# Main.net
KiCad netlist of a schematic drawn in Altium Designer
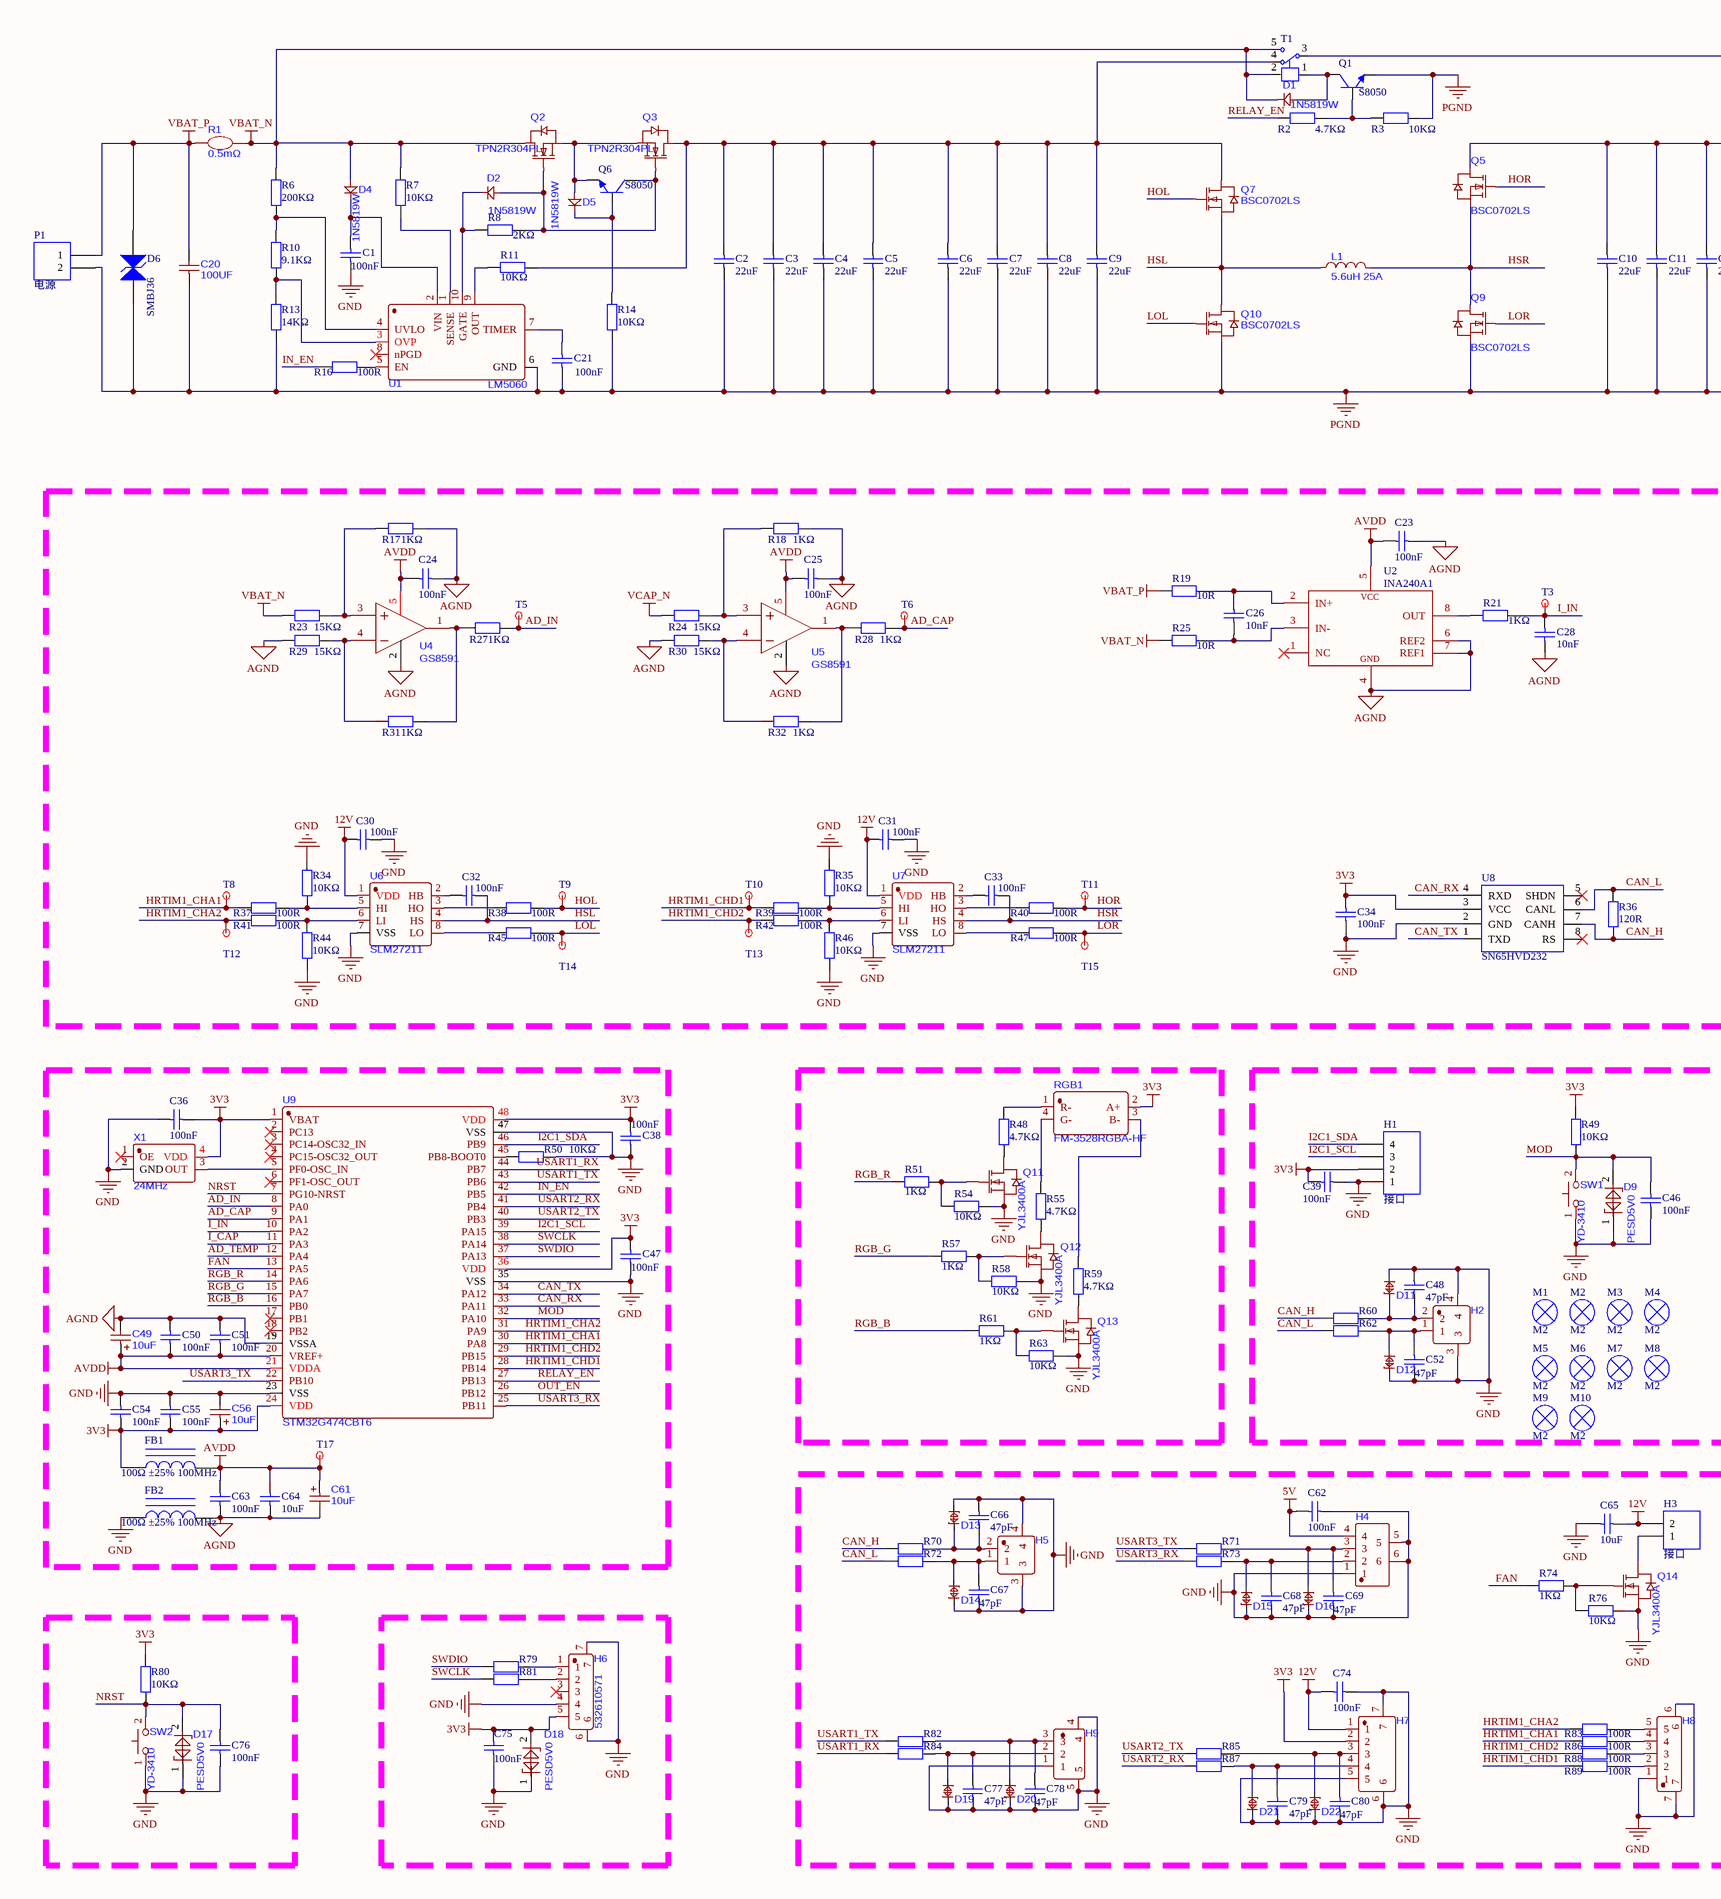
[diagram p0: Main.SchDoc, left]
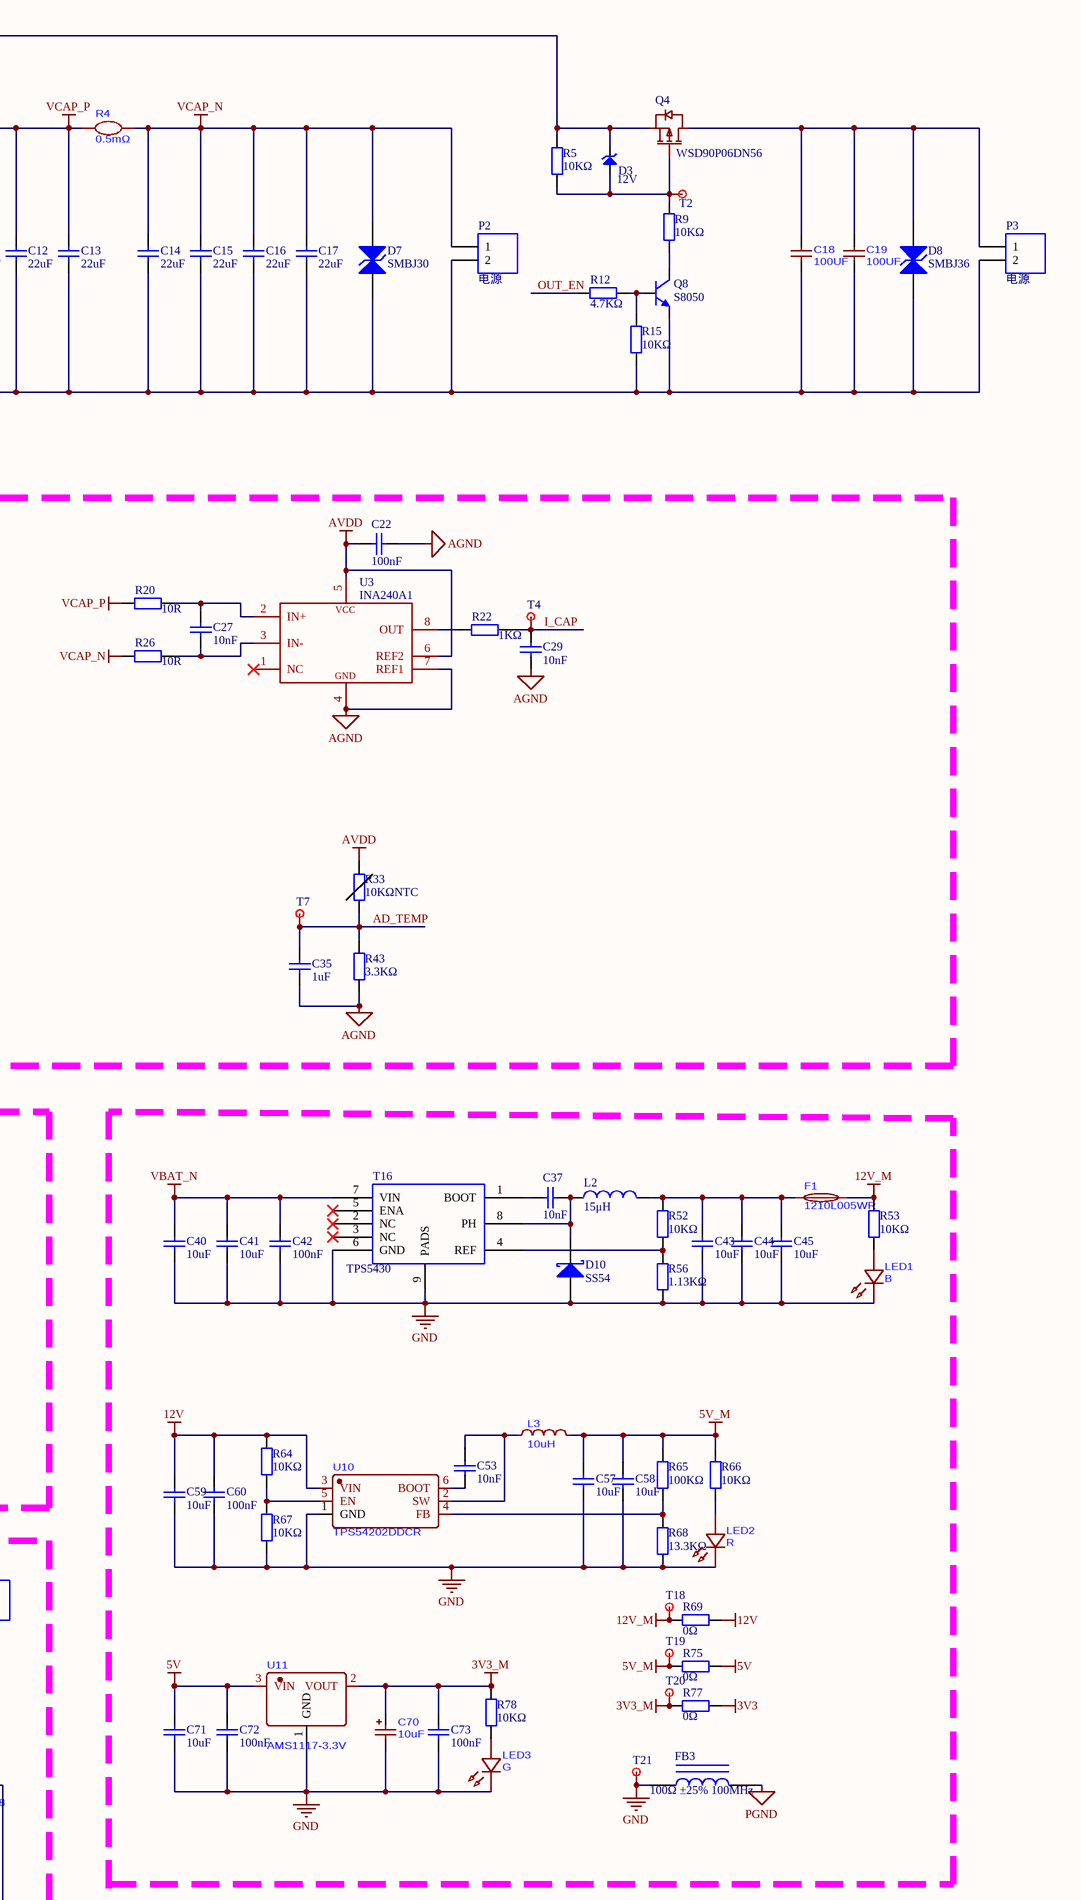
[diagram p1: Main.SchDoc, right]

(export (version "E")
  (design (tool "Eeschema 10.0.6"))
  (components
    (comp (ref "C1")
      (value "100nF")
      (footprint "0402_C")
      (description "贴片电容")
      (libsource (lib "Miscellaneous Devices LC") (part "0402 10nF (103) 10% 50V"))
    )
    (comp (ref "C2")
      (value "22uF")
      (footprint "1206_C")
      (description "贴片电容")
      (libsource (lib "Miscellaneous Devices LC") (part "1206 100nF (104) 10% 50V"))
    )
    (comp (ref "C3")
      (value "22uF")
      (footprint "1206_C")
      (description "贴片电容")
      (libsource (lib "Miscellaneous Devices LC") (part "1206 100nF (104) 10% 50V"))
    )
    (comp (ref "C4")
      (value "22uF")
      (footprint "1206_C")
      (description "贴片电容")
      (libsource (lib "Miscellaneous Devices LC") (part "1206 100nF (104) 10% 50V"))
    )
    (comp (ref "C5")
      (value "22uF")
      (footprint "1206_C")
      (description "贴片电容")
      (libsource (lib "Miscellaneous Devices LC") (part "1206 100nF (104) 10% 50V"))
    )
    (comp (ref "C6")
      (value "22uF")
      (footprint "1206_C")
      (description "贴片电容")
      (libsource (lib "Miscellaneous Devices LC") (part "1206 100nF (104) 10% 50V"))
    )
    (comp (ref "C7")
      (value "22uF")
      (footprint "1206_C")
      (description "贴片电容")
      (libsource (lib "Miscellaneous Devices LC") (part "1206 100nF (104) 10% 50V"))
    )
    (comp (ref "C8")
      (value "22uF")
      (footprint "1206_C")
      (description "贴片电容")
      (libsource (lib "Miscellaneous Devices LC") (part "1206 100nF (104) 10% 50V"))
    )
    (comp (ref "C9")
      (value "22uF")
      (footprint "1206_C")
      (description "贴片电容")
      (libsource (lib "Miscellaneous Devices LC") (part "1206 100nF (104) 10% 50V"))
    )
    (comp (ref "C10")
      (value "22uF")
      (footprint "1206_C")
      (description "贴片电容")
      (libsource (lib "Miscellaneous Devices LC") (part "1206 100nF (104) 10% 50V"))
    )
    (comp (ref "C11")
      (value "22uF")
      (footprint "1206_C")
      (description "贴片电容")
      (libsource (lib "Miscellaneous Devices LC") (part "1206 100nF (104) 10% 50V"))
    )
    (comp (ref "C12")
      (value "22uF")
      (footprint "1206_C")
      (description "贴片电容")
      (libsource (lib "Miscellaneous Devices LC") (part "1206 100nF (104) 10% 50V"))
    )
    (comp (ref "C13")
      (value "22uF")
      (footprint "1206_C")
      (description "贴片电容")
      (libsource (lib "Miscellaneous Devices LC") (part "1206 100nF (104) 10% 50V"))
    )
    (comp (ref "C14")
      (value "22uF")
      (footprint "1206_C")
      (description "贴片电容")
      (libsource (lib "Miscellaneous Devices LC") (part "1206 100nF (104) 10% 50V"))
    )
    (comp (ref "C15")
      (value "22uF")
      (footprint "1206_C")
      (description "贴片电容")
      (libsource (lib "Miscellaneous Devices LC") (part "1206 100nF (104) 10% 50V"))
    )
    (comp (ref "C16")
      (value "22uF")
      (footprint "1206_C")
      (description "贴片电容")
      (libsource (lib "Miscellaneous Devices LC") (part "1206 100nF (104) 10% 50V"))
    )
    (comp (ref "C17")
      (value "22uF")
      (footprint "1206_C")
      (description "贴片电容")
      (libsource (lib "Miscellaneous Devices LC") (part "1206 100nF (104) 10% 50V"))
    )
    (comp (ref "C18")
      (value "100UF")
      (footprint "C1812")
      (description "电容")
      (libsource (lib "JiangCi") (part "100UF/50V-1812"))
    )
    (comp (ref "C19")
      (value "100UF")
      (footprint "C1812")
      (description "电容")
      (libsource (lib "JiangCi") (part "100UF/50V-1812"))
    )
    (comp (ref "C20")
      (value "100UF")
      (footprint "C1812")
      (description "电容")
      (libsource (lib "JiangCi") (part "100UF/50V-1812"))
    )
    (comp (ref "C21")
      (value "100nF")
      (footprint "0402_C")
      (description "贴片电容")
      (libsource (lib "Miscellaneous Devices LC") (part "0402 10nF (103) 10% 50V"))
    )
    (comp (ref "C22")
      (value "100nF")
      (footprint "0402_C")
      (description "贴片电容")
      (libsource (lib "Miscellaneous Devices LC") (part "0402 10nF (103) 10% 50V"))
    )
    (comp (ref "C23")
      (value "100nF")
      (footprint "0402_C")
      (description "贴片电容")
      (libsource (lib "Miscellaneous Devices LC") (part "0402 10nF (103) 10% 50V"))
    )
    (comp (ref "C24")
      (value "100nF")
      (footprint "0402_C")
      (description "贴片电容")
      (libsource (lib "Miscellaneous Devices LC") (part "0402 10nF (103) 10% 50V"))
    )
    (comp (ref "C25")
      (value "100nF")
      (footprint "0402_C")
      (description "贴片电容")
      (libsource (lib "Miscellaneous Devices LC") (part "0402 10nF (103) 10% 50V"))
    )
    (comp (ref "C26")
      (value "10nF")
      (footprint "0402_C")
      (description "贴片电容")
      (libsource (lib "Miscellaneous Devices LC") (part "0402 10nF (103) 10% 50V"))
    )
    (comp (ref "C27")
      (value "10nF")
      (footprint "0402_C")
      (description "贴片电容")
      (libsource (lib "Miscellaneous Devices LC") (part "0402 10nF (103) 10% 50V"))
    )
    (comp (ref "C28")
      (value "10nF")
      (footprint "0402_C")
      (description "贴片电容")
      (libsource (lib "Miscellaneous Devices LC") (part "0402 10nF (103) 10% 50V"))
    )
    (comp (ref "C29")
      (value "10nF")
      (footprint "0402_C")
      (description "贴片电容")
      (libsource (lib "Miscellaneous Devices LC") (part "0402 10nF (103) 10% 50V"))
    )
    (comp (ref "C30")
      (value "100nF")
      (footprint "0402_C")
      (description "贴片电容")
      (libsource (lib "Miscellaneous Devices LC") (part "0402 10nF (103) 10% 50V"))
    )
    (comp (ref "C31")
      (value "100nF")
      (footprint "0402_C")
      (description "贴片电容")
      (libsource (lib "Miscellaneous Devices LC") (part "0402 10nF (103) 10% 50V"))
    )
    (comp (ref "C32")
      (value "100nF")
      (footprint "0402_C")
      (description "贴片电容")
      (libsource (lib "Miscellaneous Devices LC") (part "0402 10nF (103) 10% 50V"))
    )
    (comp (ref "C33")
      (value "100nF")
      (footprint "0402_C")
      (description "贴片电容")
      (libsource (lib "Miscellaneous Devices LC") (part "0402 10nF (103) 10% 50V"))
    )
    (comp (ref "C34")
      (value "100nF")
      (footprint "0402_C")
      (description "贴片电容")
      (libsource (lib "Miscellaneous Devices LC") (part "0402 10nF (103) 10% 50V"))
    )
    (comp (ref "C35")
      (value "1uF")
      (footprint "0402_C")
      (description "贴片电容")
      (libsource (lib "Miscellaneous Devices LC") (part "0402 100nF (104) 10% 16V"))
    )
    (comp (ref "C36")
      (value "100nF")
      (footprint "0402_C")
      (description "贴片电容")
      (libsource (lib "Miscellaneous Devices LC") (part "0402 100nF (104) 10% 16V"))
    )
    (comp (ref "C37")
      (value "10nF")
      (footprint "0402_C")
      (description "贴片电容")
      (libsource (lib "Miscellaneous Devices LC") (part "0402 10nF (103) 10% 50V"))
    )
    (comp (ref "C38")
      (value "100nF")
      (footprint "0402_C")
      (description "贴片电容")
      (libsource (lib "Miscellaneous Devices LC") (part "0402 100nF (104) 10% 16V"))
    )
    (comp (ref "C39")
      (value "100nF")
      (footprint "0402_C")
      (description "贴片电容")
      (libsource (lib "Miscellaneous Devices LC") (part "0402 100nF (104) 10% 16V"))
    )
    (comp (ref "C40")
      (value "10uF")
      (footprint "1206_C")
      (description "贴片电容")
      (libsource (lib "Miscellaneous Devices LC") (part "1206 10uF (106) 10% 50V"))
    )
    (comp (ref "C41")
      (value "10uF")
      (footprint "1206_C")
      (description "贴片电容")
      (libsource (lib "Miscellaneous Devices LC") (part "1206 10uF (106) 10% 50V"))
    )
    (comp (ref "C42")
      (value "100nF")
      (footprint "0603_C")
      (description "贴片电容")
      (libsource (lib "Miscellaneous Devices LC") (part "0603 100nF (104) 10% 50V"))
    )
    (comp (ref "C43")
      (value "10uF")
      (footprint "1206_C")
      (description "贴片电容")
      (libsource (lib "Miscellaneous Devices LC") (part "1206 10uF (106) 10% 50V"))
    )
    (comp (ref "C44")
      (value "10uF")
      (footprint "1206_C")
      (description "贴片电容")
      (libsource (lib "Miscellaneous Devices LC") (part "1206 10uF (106) 10% 50V"))
    )
    (comp (ref "C45")
      (value "10uF")
      (footprint "1206_C")
      (description "贴片电容")
      (libsource (lib "Miscellaneous Devices LC") (part "1206 10uF (106) 10% 50V"))
    )
    (comp (ref "C46")
      (value "100nF")
      (footprint "0402_C")
      (description "贴片电容")
      (libsource (lib "Miscellaneous Devices LC") (part "0402 100nF (104) 10% 16V"))
    )
    (comp (ref "C47")
      (value "100nF")
      (footprint "0402_C")
      (description "贴片电容")
      (libsource (lib "Miscellaneous Devices LC") (part "0402 100nF (104) 10% 16V"))
    )
    (comp (ref "C48")
      (value "47pF")
      (footprint "0402_C")
      (description "贴片电容")
      (libsource (lib "Miscellaneous Devices LC") (part "0402 47pF (470) 5% 50V"))
    )
    (comp (ref "C49")
      (value "10uF")
      (footprint "CAP-SMD_L3.2-W1.6-RD-C7171")
      (libsource (lib "JiangCi") (part "3216钽电容"))
    )
    (comp (ref "C50")
      (value "100nF")
      (footprint "0402_C")
      (description "贴片电容")
      (libsource (lib "Miscellaneous Devices LC") (part "0402 100nF (104) 10% 16V"))
    )
    (comp (ref "C51")
      (value "100nF")
      (footprint "0402_C")
      (description "贴片电容")
      (libsource (lib "Miscellaneous Devices LC") (part "0402 100nF (104) 10% 16V"))
    )
    (comp (ref "C52")
      (value "47pF")
      (footprint "0402_C")
      (description "贴片电容")
      (libsource (lib "Miscellaneous Devices LC") (part "0402 47pF (470) 5% 50V"))
    )
    (comp (ref "C53")
      (value "10nF")
      (footprint "0402_C")
      (description "贴片电容")
      (libsource (lib "Miscellaneous Devices LC") (part "0402 10nF (103) 10% 50V"))
    )
    (comp (ref "C54")
      (value "100nF")
      (footprint "0402_C")
      (description "贴片电容")
      (libsource (lib "Miscellaneous Devices LC") (part "0402 100nF (104) 10% 16V"))
    )
    (comp (ref "C55")
      (value "100nF")
      (footprint "0402_C")
      (description "贴片电容")
      (libsource (lib "Miscellaneous Devices LC") (part "0402 100nF (104) 10% 16V"))
    )
    (comp (ref "C56")
      (value "10uF")
      (footprint "CAP-SMD_L3.2-W1.6-RD-C7171")
      (libsource (lib "JiangCi") (part "3216钽电容"))
    )
    (comp (ref "C57")
      (value "10uF")
      (footprint "1206_C")
      (description "贴片电容")
      (libsource (lib "Miscellaneous Devices LC") (part "1206 10uF (106) 10% 50V"))
    )
    (comp (ref "C58")
      (value "10uF")
      (footprint "1206_C")
      (description "贴片电容")
      (libsource (lib "Miscellaneous Devices LC") (part "1206 10uF (106) 10% 50V"))
    )
    (comp (ref "C59")
      (value "10uF")
      (footprint "1206_C")
      (description "贴片电容")
      (libsource (lib "Miscellaneous Devices LC") (part "1206 10uF (106) 10% 50V"))
    )
    (comp (ref "C60")
      (value "100nF")
      (footprint "0603_C")
      (description "贴片电容")
      (libsource (lib "Miscellaneous Devices LC") (part "0603 100nF (104) 10% 50V"))
    )
    (comp (ref "C61")
      (value "10uF")
      (footprint "CAP-SMD_L3.2-W1.6-RD-C7171")
      (libsource (lib "JiangCi") (part "3216钽电容"))
    )
    (comp (ref "C62")
      (value "100nF")
      (footprint "0402_C")
      (description "贴片电容")
      (libsource (lib "Miscellaneous Devices LC") (part "0402 100nF (104) 10% 16V"))
    )
    (comp (ref "C63")
      (value "100nF")
      (footprint "0402_C")
      (description "贴片电容")
      (libsource (lib "Miscellaneous Devices LC") (part "0402 100nF (104) 10% 16V"))
    )
    (comp (ref "C64")
      (value "10uF")
      (footprint "0402_C")
      (description "贴片电容")
      (libsource (lib "Miscellaneous Devices LC") (part "0402 100nF (104) 10% 16V"))
    )
    (comp (ref "C65")
      (value "10uF")
      (footprint "1206_C")
      (description "贴片电容")
      (libsource (lib "Miscellaneous Devices LC") (part "1206 10uF (106) 10% 50V"))
    )
    (comp (ref "C66")
      (value "47pF")
      (footprint "0402_C")
      (description "贴片电容")
      (libsource (lib "Miscellaneous Devices LC") (part "0402 47pF (470) 5% 50V"))
    )
    (comp (ref "C67")
      (value "47pF")
      (footprint "0402_C")
      (description "贴片电容")
      (libsource (lib "Miscellaneous Devices LC") (part "0402 47pF (470) 5% 50V"))
    )
    (comp (ref "C68")
      (value "47pF")
      (footprint "0402_C")
      (description "贴片电容")
      (libsource (lib "Miscellaneous Devices LC") (part "0402 47pF (470) 5% 50V"))
    )
    (comp (ref "C69")
      (value "47pF")
      (footprint "0402_C")
      (description "贴片电容")
      (libsource (lib "Miscellaneous Devices LC") (part "0402 47pF (470) 5% 50V"))
    )
    (comp (ref "C70")
      (value "10uF")
      (footprint "CAP-SMD_L3.2-W1.6-RD-C7171")
      (libsource (lib "JiangCi") (part "3216钽电容"))
    )
    (comp (ref "C71")
      (value "10uF")
      (footprint "0603_C")
      (description "贴片电容")
      (libsource (lib "Miscellaneous Devices LC") (part "0603 100nF (104) 10% 50V"))
    )
    (comp (ref "C72")
      (value "100nF")
      (footprint "0603_C")
      (description "贴片电容")
      (libsource (lib "Miscellaneous Devices LC") (part "0603 100nF (104) 10% 50V"))
    )
    (comp (ref "C73")
      (value "100nF")
      (footprint "0603_C")
      (description "贴片电容")
      (libsource (lib "Miscellaneous Devices LC") (part "0603 100nF (104) 10% 50V"))
    )
    (comp (ref "C74")
      (value "100nF")
      (footprint "0402_C")
      (description "贴片电容")
      (libsource (lib "Miscellaneous Devices LC") (part "0402 100nF (104) 10% 16V"))
    )
    (comp (ref "C75")
      (value "100nF")
      (footprint "0402_C")
      (description "贴片电容")
      (libsource (lib "Miscellaneous Devices LC") (part "0402 100nF (104) 10% 16V"))
    )
    (comp (ref "C76")
      (value "100nF")
      (footprint "0402_C")
      (description "贴片电容")
      (libsource (lib "Miscellaneous Devices LC") (part "0402 100nF (104) 10% 16V"))
    )
    (comp (ref "C77")
      (value "47pF")
      (footprint "0402_C")
      (description "贴片电容")
      (libsource (lib "Miscellaneous Devices LC") (part "0402 47pF (470) 5% 50V"))
    )
    (comp (ref "C78")
      (value "47pF")
      (footprint "0402_C")
      (description "贴片电容")
      (libsource (lib "Miscellaneous Devices LC") (part "0402 47pF (470) 5% 50V"))
    )
    (comp (ref "C79")
      (value "47pF")
      (footprint "0402_C")
      (description "贴片电容")
      (libsource (lib "Miscellaneous Devices LC") (part "0402 47pF (470) 5% 50V"))
    )
    (comp (ref "C80")
      (value "47pF")
      (footprint "0402_C")
      (description "贴片电容")
      (libsource (lib "Miscellaneous Devices LC") (part "0402 47pF (470) 5% 50V"))
    )
    (comp (ref "D1")
      (value "1N5819W")
      (footprint "SOD-123_L2.8-W1.8-LS3.7-RD")
      (description "二极管")
      (libsource (lib "JiangCi") (part "1N5819W"))
    )
    (comp (ref "D2")
      (value "1N5819W")
      (footprint "SOD-123_L2.8-W1.8-LS3.7-RD")
      (libsource (lib "JiangCi") (part "1N5819W"))
    )
    (comp (ref "D3")
      (value "12V")
      (footprint "SOD-123")
      (description "稳压二极管")
      (libsource (lib "RM2020原理图库v1.3 (1)") (part "稳压二极管"))
    )
    (comp (ref "D4")
      (value "1N5819W")
      (footprint "SOD-123_L2.8-W1.8-LS3.7-RD")
      (libsource (lib "JiangCi") (part "1N5819W"))
    )
    (comp (ref "D5")
      (value "1N5819W")
      (footprint "SOD-123_L2.8-W1.8-LS3.7-RD")
      (libsource (lib "JiangCi") (part "1N5819W"))
    )
    (comp (ref "D6")
      (value "SMBJ36")
      (footprint "SMB(DO-214AA)_S1")
      (description "TVS")
      (libsource (lib "Miscellaneous Devices LC") (part "SMB/DO-214AA P6SMB6.8CA"))
    )
    (comp (ref "D7")
      (value "SMBJ30")
      (footprint "SMB(DO-214AA)_S1")
      (description "TVS")
      (libsource (lib "Miscellaneous Devices LC") (part "SMB/DO-214AA P6SMB6.8CA"))
    )
    (comp (ref "D8")
      (value "SMBJ36")
      (footprint "SMB(DO-214AA)_S1")
      (description "TVS")
      (libsource (lib "Miscellaneous Devices LC") (part "SMB/DO-214AA P6SMB6.8CA"))
    )
    (comp (ref "D9")
      (value "PESD5V0")
      (footprint "SOD-882_L1.0-W0.6-BI")
      (libsource (lib "") (part "PESD5V0F1BL,315_1"))
    )
    (comp (ref "D10")
      (value "SS54")
      (footprint "SS54")
      (description "Schottky Diode")
      (fields (field (name "PUBLISHER") "Altium Limited"))
      (libsource (lib "RM2020原理图库v1.3 (1)") (part "SS54"))
    )
    (comp (ref "D11")
      (value "PESD5V0F1BL,315")
      (footprint "SOD-882_L1.0-W0.6-BI")
      (libsource (lib "JiangCi") (part "PESD5V0F1BL,315"))
    )
    (comp (ref "D12")
      (value "PESD5V0F1BL,315")
      (footprint "SOD-882_L1.0-W0.6-BI")
      (libsource (lib "JiangCi") (part "PESD5V0F1BL,315"))
    )
    (comp (ref "D13")
      (value "PESD5V0F1BL,315")
      (footprint "SOD-882_L1.0-W0.6-BI")
      (libsource (lib "JiangCi") (part "PESD5V0F1BL,315"))
    )
    (comp (ref "D14")
      (value "PESD5V0F1BL,315")
      (footprint "SOD-882_L1.0-W0.6-BI")
      (libsource (lib "JiangCi") (part "PESD5V0F1BL,315"))
    )
    (comp (ref "D15")
      (value "PESD5V0F1BL,315")
      (footprint "SOD-882_L1.0-W0.6-BI")
      (libsource (lib "JiangCi") (part "PESD5V0F1BL,315"))
    )
    (comp (ref "D16")
      (value "PESD5V0F1BL,315")
      (footprint "SOD-882_L1.0-W0.6-BI")
      (libsource (lib "JiangCi") (part "PESD5V0F1BL,315"))
    )
    (comp (ref "D17")
      (value "PESD5V0")
      (footprint "SOD-882_L1.0-W0.6-BI")
      (libsource (lib "") (part "PESD5V0F1BL,315_1"))
    )
    (comp (ref "D18")
      (value "PESD5V0")
      (footprint "SOD-882_L1.0-W0.6-BI")
      (libsource (lib "") (part "PESD5V0F1BL,315_1"))
    )
    (comp (ref "D19")
      (value "PESD5V0F1BL,315")
      (footprint "SOD-882_L1.0-W0.6-BI")
      (libsource (lib "JiangCi") (part "PESD5V0F1BL,315"))
    )
    (comp (ref "D20")
      (value "PESD5V0F1BL,315")
      (footprint "SOD-882_L1.0-W0.6-BI")
      (libsource (lib "JiangCi") (part "PESD5V0F1BL,315"))
    )
    (comp (ref "D21")
      (value "PESD5V0F1BL,315")
      (footprint "SOD-882_L1.0-W0.6-BI")
      (libsource (lib "JiangCi") (part "PESD5V0F1BL,315"))
    )
    (comp (ref "D22")
      (value "PESD5V0F1BL,315")
      (footprint "SOD-882_L1.0-W0.6-BI")
      (libsource (lib "JiangCi") (part "PESD5V0F1BL,315"))
    )
    (comp (ref "F1") (value "1210L005WR") (footprint "F1210") (libsource (lib "JiangCi") (part "1210L005WR")))
    (comp (ref "FB1")
      (value "100Ω ±25% 100MHz")
      (footprint "0805_L")
      (description "贴片磁珠")
      (libsource (lib "Miscellaneous Devices LC") (part "0805 100Ω 25% 100MHz"))
    )
    (comp (ref "FB2")
      (value "100Ω ±25% 100MHz")
      (footprint "0805_L")
      (description "贴片磁珠")
      (libsource (lib "Miscellaneous Devices LC") (part "0805 100Ω 25% 100MHz"))
    )
    (comp (ref "FB3")
      (value "100Ω ±25% 100MHz")
      (footprint "0805_L")
      (description "贴片磁珠")
      (libsource (lib "Miscellaneous Devices LC") (part "0805 100Ω 25% 100MHz"))
    )
    (comp (ref "H1")
      (value "接口")
      (footprint "排母1X4")
      (description "Header, 4-Pin")
      (fields (field (name "PUBLISHER") "Altium Limited"))
      (libsource (lib "RM2020原理图库v1.3 (1)") (part "排母1X4"))
    )
    (comp (ref "H2")
      (value "GH1.25-2PW")
      (footprint "CONN-TH_2P-P1.25_XUNPU_WAFER-GH1.25-2PLB")
      (libsource (lib "JiangCi") (part "GH1.25-2PW"))
    )
    (comp (ref "H3")
      (value "接口")
      (footprint "XH2.54-2P")
      (description "Header, 2-Pin")
      (fields (field (name "PUBLISHER") "Altium Limited"))
      (libsource (lib "RM2020原理图库v1.3 (1)") (part "XH2.54 2P"))
    )
    (comp (ref "H4")
      (value "53261-0471")
      (footprint "CONN-SMD_4P-P1.25_53261-0471")
      (libsource (lib "JiangCi") (part "53261-0471"))
    )
    (comp (ref "H5")
      (value "GH1.25-2PW")
      (footprint "CONN-TH_2P-P1.25_XUNPU_WAFER-GH1.25-2PLB")
      (libsource (lib "JiangCi") (part "GH1.25-2PW"))
    )
    (comp (ref "H6")
      (value "532610571")
      (footprint "CONN-SMD_5P-P1.25_532610571-2")
      (libsource (lib "JiangCi") (part "532610571"))
    )
    (comp (ref "H7")
      (value "GH1.25-5PW")
      (footprint "CONN-SMD_5P-P1.25_DEALON_L125WVS-05PW")
      (libsource (lib "JiangCi") (part "GH1.25-5PW"))
    )
    (comp (ref "H8")
      (value "532610571")
      (footprint "CONN-SMD_5P-P1.25_532610571-2")
      (libsource (lib "JiangCi") (part "532610571"))
    )
    (comp (ref "H9")
      (value "GH1.25-3PW")
      (footprint "CONN-SMD_GH1.25-3P")
      (libsource (lib "JiangCi") (part "GH1.25-3PW"))
    )
    (comp (ref "L1")
      (value "5.6uH 25A")
      (footprint "IND-SMD_L18.2-W18.2")
      (libsource (lib "JiangCi") (part "功率电感"))
    )
    (comp (ref "L2")
      (value "15μH")
      (footprint "电感")
      (description "贴片电感")
      (fields (field (name "PUBLISHER") "Altium Limited"))
      (libsource (lib "RM2020原理图库v1.3 (1)") (part "15μH"))
    )
    (comp (ref "L3")
      (value "10uH")
      (footprint "IND-SMD_L2.5-W2.0_WPN252012H")
      (libsource (lib "JiangCi") (part "10uH 1.1A"))
    )
    (comp (ref "LED1")
      (value "B")
      (footprint "LED0402-RD")
      (libsource (lib "JiangCi") (part "TJ-S1005CL4T5ALC3DW-A5"))
    )
    (comp (ref "LED2")
      (value "R")
      (footprint "LED0402-RD")
      (libsource (lib "JiangCi") (part "TJ-S1005CL4T5ALC3DW-A5"))
    )
    (comp (ref "LED3")
      (value "G")
      (footprint "LED0402-RD")
      (libsource (lib "JiangCi") (part "TJ-S1005CL4T5ALC3DW-A5"))
    )
    (comp (ref "M1")
      (value "M2")
      (footprint "M2.5螺母")
      (description "M2焊接螺母")
      (libsource (lib "JiangCi") (part "M2螺母"))
    )
    (comp (ref "M2")
      (value "M2")
      (footprint "M2.5螺母")
      (description "M2焊接螺母")
      (libsource (lib "JiangCi") (part "M2螺母"))
    )
    (comp (ref "M3")
      (value "M2")
      (footprint "M2.5螺母")
      (description "M2焊接螺母")
      (libsource (lib "JiangCi") (part "M2螺母"))
    )
    (comp (ref "M4")
      (value "M2")
      (footprint "M2.5螺母")
      (description "M2焊接螺母")
      (libsource (lib "JiangCi") (part "M2螺母"))
    )
    (comp (ref "M5")
      (value "M2")
      (footprint "M2.5螺母")
      (description "M2焊接螺母")
      (libsource (lib "JiangCi") (part "M2螺母"))
    )
    (comp (ref "M6")
      (value "M2")
      (footprint "M2.5螺母")
      (description "M2焊接螺母")
      (libsource (lib "JiangCi") (part "M2螺母"))
    )
    (comp (ref "M7")
      (value "M2")
      (footprint "M2.5螺母")
      (description "M2焊接螺母")
      (libsource (lib "JiangCi") (part "M2螺母"))
    )
    (comp (ref "M8")
      (value "M2")
      (footprint "M2.5螺母")
      (description "M2焊接螺母")
      (libsource (lib "JiangCi") (part "M2螺母"))
    )
    (comp (ref "M9")
      (value "M2")
      (footprint "M2.5螺母")
      (description "M2焊接螺母")
      (libsource (lib "JiangCi") (part "M2螺母"))
    )
    (comp (ref "M10")
      (value "M2")
      (footprint "M2.5螺母")
      (description "M2焊接螺母")
      (libsource (lib "JiangCi") (part "M2螺母"))
    )
    (comp (ref "P1")
      (value "电源")
      (footprint "XT30PW-M")
      (description "Header, 2-Pin")
      (fields (field (name "PUBLISHER") "Altium Limited"))
      (libsource (lib "") (part "XT30公头卧式_1"))
    )
    (comp (ref "P2")
      (value "电源")
      (footprint "XT30PW-M")
      (description "Header, 2-Pin")
      (fields (field (name "PUBLISHER") "Altium Limited"))
      (libsource (lib "RM2020原理图库v1.3 (1)") (part "XT30公头卧式"))
    )
    (comp (ref "P3")
      (value "电源")
      (footprint "XT30PW-M")
      (description "Header, 2-Pin")
      (fields (field (name "PUBLISHER") "Altium Limited"))
      (libsource (lib "RM2020原理图库v1.3 (1)") (part "XT30公头卧式"))
    )
    (comp (ref "Q1")
      (value "S8050")
      (footprint "SOT-23")
      (description "三极管")
      (libsource (lib "RM2020原理图库v1.3 (1)") (part "NPN三极管"))
    )
    (comp (ref "Q2")
      (value "TPN2R304PL")
      (footprint "TSON-8_L3.1-W3.1-P0.65-LS3.3-BL-EP")
      (libsource (lib "JiangCi") (part "TPN2R304PL"))
    )
    (comp (ref "Q3")
      (value "TPN2R304PL")
      (footprint "TSON-8_L3.1-W3.1-P0.65-LS3.3-BL-EP")
      (libsource (lib "JiangCi") (part "TPN2R304PL"))
    )
    (comp (ref "Q4")
      (value "WSD90P06DN56")
      (footprint "DFN-8_L5.8-W4.9-P1.27-LS6.0-BL-2")
      (description "PMOS")
      (libsource (lib "JiangCi") (part "WSD90P06DN56"))
    )
    (comp (ref "Q5")
      (value "BSC0702LS")
      (footprint "PG-TDSON-8_L5.0-W6.0-P1.27-BL-EP")
      (libsource (lib "JiangCi") (part "BSC0702LS"))
    )
    (comp (ref "Q6")
      (value "S8050")
      (footprint "SOT-23")
      (description "三极管")
      (libsource (lib "RM2020原理图库v1.3 (1)") (part "NPN三极管"))
    )
    (comp (ref "Q7")
      (value "BSC0702LS")
      (footprint "PG-TDSON-8_L5.0-W6.0-P1.27-BL-EP")
      (libsource (lib "JiangCi") (part "BSC0702LS"))
    )
    (comp (ref "Q8")
      (value "S8050")
      (footprint "SOT-23")
      (description "三极管")
      (libsource (lib "RM2020原理图库v1.3 (1)") (part "NPN三极管"))
    )
    (comp (ref "Q9")
      (value "BSC0702LS")
      (footprint "PG-TDSON-8_L5.0-W6.0-P1.27-BL-EP")
      (libsource (lib "JiangCi") (part "BSC0702LS"))
    )
    (comp (ref "Q10")
      (value "BSC0702LS")
      (footprint "PG-TDSON-8_L5.0-W6.0-P1.27-BL-EP")
      (libsource (lib "JiangCi") (part "BSC0702LS"))
    )
    (comp (ref "Q11")
      (value "YJL3400A")
      (footprint "SOT-23-3_L2.9-W1.3-P1.90-LS2.4-BR")
      (libsource (lib "JiangCi") (part "YJL3400A"))
    )
    (comp (ref "Q12")
      (value "YJL3400A")
      (footprint "SOT-23-3_L2.9-W1.3-P1.90-LS2.4-BR")
      (libsource (lib "JiangCi") (part "YJL3400A"))
    )
    (comp (ref "Q13")
      (value "YJL3400A")
      (footprint "SOT-23-3_L2.9-W1.3-P1.90-LS2.4-BR")
      (libsource (lib "JiangCi") (part "YJL3400A"))
    )
    (comp (ref "Q14")
      (value "YJL3400A")
      (footprint "SOT-23-3_L2.9-W1.3-P1.90-LS2.4-BR")
      (libsource (lib "JiangCi") (part "YJL3400A"))
    )
    (comp (ref "R1")
      (value "0.5mΩ")
      (footprint "RES-SMD_L6.4-W3.2_C500733")
      (description "2512采样电阻")
      (libsource (lib "JiangCi") (part "2512"))
    )
    (comp (ref "R2")
      (value "4.7KΩ")
      (footprint "0402_R")
      (description "贴片电阻")
      (libsource (lib "") (part "0402 10KΩ (1002) 1%_1"))
    )
    (comp (ref "R3")
      (value "10KΩ")
      (footprint "0402_R")
      (description "贴片电阻")
      (libsource (lib "") (part "0402 10KΩ (1002) 1%_1"))
    )
    (comp (ref "R4")
      (value "0.5mΩ")
      (footprint "RES-SMD_L6.4-W3.2_C500733")
      (description "2512采样电阻")
      (libsource (lib "JiangCi") (part "2512"))
    )
    (comp (ref "R5")
      (value "10KΩ")
      (footprint "0402_R")
      (description "贴片电阻")
      (libsource (lib "Miscellaneous Devices LC") (part "0402 10KΩ (1002) 1%"))
    )
    (comp (ref "R6")
      (value "200KΩ")
      (footprint "0402_R")
      (description "贴片电阻")
      (libsource (lib "") (part "0402 10KΩ (1002) 1%_2"))
    )
    (comp (ref "R7")
      (value "10KΩ")
      (footprint "0402_R")
      (description "贴片电阻")
      (libsource (lib "") (part "0402 10KΩ (1002) 1%_2"))
    )
    (comp (ref "R8")
      (value "2KΩ")
      (footprint "0402_R")
      (description "贴片电阻")
      (libsource (lib "") (part "0402 10KΩ (1002) 1%_3"))
    )
    (comp (ref "R9")
      (value "10KΩ")
      (footprint "0402_R")
      (description "贴片电阻")
      (libsource (lib "Miscellaneous Devices LC") (part "0402 10KΩ (1002) 1%"))
    )
    (comp (ref "R10")
      (value "9.1KΩ")
      (footprint "0402_R")
      (description "贴片电阻")
      (libsource (lib "") (part "0402 10KΩ (1002) 1%_2"))
    )
    (comp (ref "R11")
      (value "10KΩ")
      (footprint "0402_R")
      (description "贴片电阻")
      (libsource (lib "") (part "0402 10KΩ (1002) 1%_3"))
    )
    (comp (ref "R12")
      (value "4.7KΩ")
      (footprint "0402_R")
      (description "贴片电阻")
      (libsource (lib "") (part "0402 10KΩ (1002) 1%_1"))
    )
    (comp (ref "R13")
      (value "14KΩ")
      (footprint "0402_R")
      (description "贴片电阻")
      (libsource (lib "") (part "0402 10KΩ (1002) 1%_2"))
    )
    (comp (ref "R14")
      (value "10KΩ")
      (footprint "0402_R")
      (description "贴片电阻")
      (libsource (lib "Miscellaneous Devices LC") (part "0402 10KΩ (1002) 1%"))
    )
    (comp (ref "R15")
      (value "10KΩ")
      (footprint "0402_R")
      (description "贴片电阻")
      (libsource (lib "Miscellaneous Devices LC") (part "0402 10KΩ (1002) 1%"))
    )
    (comp (ref "R16")
      (value "100R")
      (footprint "0402_R")
      (description "贴片电阻")
      (libsource (lib "") (part "0402 10KΩ (1002) 1%_1"))
    )
    (comp (ref "R17")
      (value "1KΩ")
      (footprint "0402_R")
      (description "贴片电阻")
      (libsource (lib "") (part "0402 10KΩ (1002) 1%_1"))
    )
    (comp (ref "R18")
      (value "1KΩ")
      (footprint "0402_R")
      (description "贴片电阻")
      (libsource (lib "") (part "0402 10KΩ (1002) 1%_1"))
    )
    (comp (ref "R19")
      (value "10R")
      (footprint "0402_R")
      (description "贴片电阻")
      (libsource (lib "") (part "0402 10KΩ (1002) 1%_1"))
    )
    (comp (ref "R20")
      (value "10R")
      (footprint "0402_R")
      (description "贴片电阻")
      (libsource (lib "") (part "0402 10KΩ (1002) 1%_1"))
    )
    (comp (ref "R21")
      (value "1KΩ")
      (footprint "0402_R")
      (description "贴片电阻")
      (libsource (lib "") (part "0402 10KΩ (1002) 1%_1"))
    )
    (comp (ref "R22")
      (value "1KΩ")
      (footprint "0402_R")
      (description "贴片电阻")
      (libsource (lib "") (part "0402 10KΩ (1002) 1%_1"))
    )
    (comp (ref "R23")
      (value "15KΩ")
      (footprint "0402_R")
      (description "贴片电阻")
      (libsource (lib "") (part "0402 10KΩ (1002) 1%_1"))
    )
    (comp (ref "R24")
      (value "15KΩ")
      (footprint "0402_R")
      (description "贴片电阻")
      (libsource (lib "") (part "0402 10KΩ (1002) 1%_1"))
    )
    (comp (ref "R25")
      (value "10R")
      (footprint "0402_R")
      (description "贴片电阻")
      (libsource (lib "") (part "0402 10KΩ (1002) 1%_1"))
    )
    (comp (ref "R26")
      (value "10R")
      (footprint "0402_R")
      (description "贴片电阻")
      (libsource (lib "") (part "0402 10KΩ (1002) 1%_1"))
    )
    (comp (ref "R27")
      (value "1KΩ")
      (footprint "0402_R")
      (description "贴片电阻")
      (libsource (lib "") (part "0402 10KΩ (1002) 1%_1"))
    )
    (comp (ref "R28")
      (value "1KΩ")
      (footprint "0402_R")
      (description "贴片电阻")
      (libsource (lib "") (part "0402 10KΩ (1002) 1%_1"))
    )
    (comp (ref "R29")
      (value "15KΩ")
      (footprint "0402_R")
      (description "贴片电阻")
      (libsource (lib "") (part "0402 10KΩ (1002) 1%_1"))
    )
    (comp (ref "R30")
      (value "15KΩ")
      (footprint "0402_R")
      (description "贴片电阻")
      (libsource (lib "") (part "0402 10KΩ (1002) 1%_1"))
    )
    (comp (ref "R31")
      (value "1KΩ")
      (footprint "0402_R")
      (description "贴片电阻")
      (libsource (lib "") (part "0402 10KΩ (1002) 1%_1"))
    )
    (comp (ref "R32")
      (value "1KΩ")
      (footprint "0402_R")
      (description "贴片电阻")
      (libsource (lib "") (part "0402 10KΩ (1002) 1%_1"))
    )
    (comp (ref "R33")
      (value "10KΩNTC")
      (footprint "0402_R")
      (description "贴片电阻")
      (libsource (lib "") (part "0402 10KΩ (1002) 1%_2"))
    )
    (comp (ref "R34")
      (value "10KΩ")
      (footprint "0402_R")
      (description "贴片电阻")
      (libsource (lib "") (part "0402 10KΩ (1002) 1%_2"))
    )
    (comp (ref "R35")
      (value "10KΩ")
      (footprint "0402_R")
      (description "贴片电阻")
      (libsource (lib "") (part "0402 10KΩ (1002) 1%_2"))
    )
    (comp (ref "R36")
      (value "120R")
      (footprint "0402_R")
      (description "贴片电阻")
      (libsource (lib "") (part "0402 10KΩ (1002) 1%_2"))
    )
    (comp (ref "R37")
      (value "100R")
      (footprint "0402_R")
      (description "贴片电阻")
      (libsource (lib "") (part "0402 10KΩ (1002) 1%_1"))
    )
    (comp (ref "R38")
      (value "100R")
      (footprint "0402_R")
      (description "贴片电阻")
      (libsource (lib "") (part "0402 10KΩ (1002) 1%_1"))
    )
    (comp (ref "R39")
      (value "100R")
      (footprint "0402_R")
      (description "贴片电阻")
      (libsource (lib "") (part "0402 10KΩ (1002) 1%_1"))
    )
    (comp (ref "R40")
      (value "100R")
      (footprint "0402_R")
      (description "贴片电阻")
      (libsource (lib "") (part "0402 10KΩ (1002) 1%_1"))
    )
    (comp (ref "R41")
      (value "100R")
      (footprint "0402_R")
      (description "贴片电阻")
      (libsource (lib "") (part "0402 10KΩ (1002) 1%_1"))
    )
    (comp (ref "R42")
      (value "100R")
      (footprint "0402_R")
      (description "贴片电阻")
      (libsource (lib "") (part "0402 10KΩ (1002) 1%_1"))
    )
    (comp (ref "R43")
      (value "3.3KΩ")
      (footprint "0402_R")
      (description "贴片电阻")
      (libsource (lib "") (part "0402 10KΩ (1002) 1%_2"))
    )
    (comp (ref "R44")
      (value "10KΩ")
      (footprint "0402_R")
      (description "贴片电阻")
      (libsource (lib "") (part "0402 10KΩ (1002) 1%_2"))
    )
    (comp (ref "R45")
      (value "100R")
      (footprint "0402_R")
      (description "贴片电阻")
      (libsource (lib "") (part "0402 10KΩ (1002) 1%_1"))
    )
    (comp (ref "R46")
      (value "10KΩ")
      (footprint "0402_R")
      (description "贴片电阻")
      (libsource (lib "") (part "0402 10KΩ (1002) 1%_2"))
    )
    (comp (ref "R47")
      (value "100R")
      (footprint "0402_R")
      (description "贴片电阻")
      (libsource (lib "") (part "0402 10KΩ (1002) 1%_1"))
    )
    (comp (ref "R48")
      (value "4.7KΩ")
      (footprint "0402_R")
      (description "贴片电阻")
      (libsource (lib "Miscellaneous Devices LC") (part "0402 10KΩ (1002) 1%"))
    )
    (comp (ref "R49")
      (value "10KΩ")
      (footprint "0402_R")
      (description "贴片电阻")
      (libsource (lib "") (part "0402 10KΩ (1002) 1%_2"))
    )
    (comp (ref "R50")
      (value "10KΩ")
      (footprint "0402_R")
      (description "贴片电阻")
      (libsource (lib "") (part "0402 10KΩ (1002) 1%_1"))
    )
    (comp (ref "R51")
      (value "1KΩ")
      (footprint "0402_R")
      (description "贴片电阻")
      (libsource (lib "") (part "0402 10KΩ (1002) 1%_3"))
    )
    (comp (ref "R52")
      (value "10KΩ")
      (footprint "0402_R")
      (description "贴片电阻")
      (libsource (lib "Miscellaneous Devices LC") (part "0402 10KΩ (1002) 1%"))
    )
    (comp (ref "R53")
      (value "10KΩ")
      (footprint "0402_R")
      (description "贴片电阻")
      (libsource (lib "Miscellaneous Devices LC") (part "0402 10KΩ (1002) 1%"))
    )
    (comp (ref "R54")
      (value "10KΩ")
      (footprint "0402_R")
      (description "贴片电阻")
      (libsource (lib "") (part "0402 10KΩ (1002) 1%_3"))
    )
    (comp (ref "R55")
      (value "4.7KΩ")
      (footprint "0402_R")
      (description "贴片电阻")
      (libsource (lib "Miscellaneous Devices LC") (part "0402 10KΩ (1002) 1%"))
    )
    (comp (ref "R56")
      (value "1.13KΩ")
      (footprint "0402_R")
      (description "贴片电阻")
      (libsource (lib "Miscellaneous Devices LC") (part "0402 3.3KΩ (3301) 1%"))
    )
    (comp (ref "R57")
      (value "1KΩ")
      (footprint "0402_R")
      (description "贴片电阻")
      (libsource (lib "") (part "0402 10KΩ (1002) 1%_3"))
    )
    (comp (ref "R58")
      (value "10KΩ")
      (footprint "0402_R")
      (description "贴片电阻")
      (libsource (lib "") (part "0402 10KΩ (1002) 1%_3"))
    )
    (comp (ref "R59")
      (value "4.7KΩ")
      (footprint "0402_R")
      (description "贴片电阻")
      (libsource (lib "Miscellaneous Devices LC") (part "0402 10KΩ (1002) 1%"))
    )
    (comp (ref "R60")
      (value "100Ω")
      (footprint "0402_R")
      (description "贴片电阻")
      (libsource (lib "") (part "0402 10KΩ (1002) 1%_3"))
    )
    (comp (ref "R61")
      (value "1KΩ")
      (footprint "0402_R")
      (description "贴片电阻")
      (libsource (lib "") (part "0402 10KΩ (1002) 1%_3"))
    )
    (comp (ref "R62")
      (value "100Ω")
      (footprint "0402_R")
      (description "贴片电阻")
      (libsource (lib "") (part "0402 10KΩ (1002) 1%_3"))
    )
    (comp (ref "R63")
      (value "10KΩ")
      (footprint "0402_R")
      (description "贴片电阻")
      (libsource (lib "") (part "0402 10KΩ (1002) 1%_3"))
    )
    (comp (ref "R64")
      (value "10KΩ")
      (footprint "0402_R")
      (description "贴片电阻")
      (libsource (lib "Miscellaneous Devices LC") (part "0402 10KΩ (1002) 1%"))
    )
    (comp (ref "R65")
      (value "100KΩ")
      (footprint "0402_R")
      (description "贴片电阻")
      (libsource (lib "Miscellaneous Devices LC") (part "0402 10KΩ (1002) 1%"))
    )
    (comp (ref "R66")
      (value "10KΩ")
      (footprint "0402_R")
      (description "贴片电阻")
      (libsource (lib "Miscellaneous Devices LC") (part "0402 10KΩ (1002) 1%"))
    )
    (comp (ref "R67")
      (value "10KΩ")
      (footprint "0402_R")
      (description "贴片电阻")
      (libsource (lib "Miscellaneous Devices LC") (part "0402 10KΩ (1002) 1%"))
    )
    (comp (ref "R68")
      (value "13.3KΩ")
      (footprint "0402_R")
      (description "贴片电阻")
      (libsource (lib "Miscellaneous Devices LC") (part "0402 10KΩ (1002) 1%"))
    )
    (comp (ref "R69")
      (value "0Ω")
      (footprint "0603_R")
      (description "贴片电阻")
      (libsource (lib "Miscellaneous Devices LC") (part "0603 0Ω (0R0) 1%"))
    )
    (comp (ref "R70")
      (value "100Ω")
      (footprint "0402_R")
      (description "贴片电阻")
      (libsource (lib "") (part "0402 10KΩ (1002) 1%_3"))
    )
    (comp (ref "R71")
      (value "100Ω")
      (footprint "0402_R")
      (description "贴片电阻")
      (libsource (lib "") (part "0402 10KΩ (1002) 1%_3"))
    )
    (comp (ref "R72")
      (value "100Ω")
      (footprint "0402_R")
      (description "贴片电阻")
      (libsource (lib "") (part "0402 10KΩ (1002) 1%_3"))
    )
    (comp (ref "R73")
      (value "100Ω")
      (footprint "0402_R")
      (description "贴片电阻")
      (libsource (lib "") (part "0402 10KΩ (1002) 1%_3"))
    )
    (comp (ref "R74")
      (value "1KΩ")
      (footprint "0402_R")
      (description "贴片电阻")
      (libsource (lib "") (part "0402 10KΩ (1002) 1%_3"))
    )
    (comp (ref "R75")
      (value "0Ω")
      (footprint "0603_R")
      (description "贴片电阻")
      (libsource (lib "Miscellaneous Devices LC") (part "0603 0Ω (0R0) 1%"))
    )
    (comp (ref "R76")
      (value "10KΩ")
      (footprint "0402_R")
      (description "贴片电阻")
      (libsource (lib "") (part "0402 10KΩ (1002) 1%_3"))
    )
    (comp (ref "R77")
      (value "0Ω")
      (footprint "0603_R")
      (description "贴片电阻")
      (libsource (lib "Miscellaneous Devices LC") (part "0603 0Ω (0R0) 1%"))
    )
    (comp (ref "R78")
      (value "10KΩ")
      (footprint "0402_R")
      (description "贴片电阻")
      (libsource (lib "Miscellaneous Devices LC") (part "0402 10KΩ (1002) 1%"))
    )
    (comp (ref "R79")
      (value "100Ω")
      (footprint "0402_R")
      (description "贴片电阻")
      (libsource (lib "") (part "0402 10KΩ (1002) 1%_3"))
    )
    (comp (ref "R80")
      (value "10KΩ")
      (footprint "0402_R")
      (description "贴片电阻")
      (libsource (lib "") (part "0402 10KΩ (1002) 1%_2"))
    )
    (comp (ref "R81")
      (value "100Ω")
      (footprint "0402_R")
      (description "贴片电阻")
      (libsource (lib "") (part "0402 10KΩ (1002) 1%_3"))
    )
    (comp (ref "R82")
      (value "100Ω")
      (footprint "0402_R")
      (description "贴片电阻")
      (libsource (lib "") (part "0402 10KΩ (1002) 1%_3"))
    )
    (comp (ref "R83")
      (value "100R")
      (footprint "0402_R")
      (description "贴片电阻")
      (libsource (lib "") (part "0402 10KΩ (1002) 1%_1"))
    )
    (comp (ref "R84")
      (value "100Ω")
      (footprint "0402_R")
      (description "贴片电阻")
      (libsource (lib "") (part "0402 10KΩ (1002) 1%_3"))
    )
    (comp (ref "R85")
      (value "100Ω")
      (footprint "0402_R")
      (description "贴片电阻")
      (libsource (lib "") (part "0402 10KΩ (1002) 1%_3"))
    )
    (comp (ref "R86")
      (value "100R")
      (footprint "0402_R")
      (description "贴片电阻")
      (libsource (lib "") (part "0402 10KΩ (1002) 1%_1"))
    )
    (comp (ref "R87")
      (value "100Ω")
      (footprint "0402_R")
      (description "贴片电阻")
      (libsource (lib "") (part "0402 10KΩ (1002) 1%_3"))
    )
    (comp (ref "R88")
      (value "100R")
      (footprint "0402_R")
      (description "贴片电阻")
      (libsource (lib "") (part "0402 10KΩ (1002) 1%_1"))
    )
    (comp (ref "R89")
      (value "100R")
      (footprint "0402_R")
      (description "贴片电阻")
      (libsource (lib "") (part "0402 10KΩ (1002) 1%_1"))
    )
    (comp (ref "RGB1")
      (value "FM-3528RGBA-HF")
      (footprint "LED-SMD_4P-L3.2-W2.8-LS3.5-BR-1")
      (libsource (lib "JiangCi") (part "FM-3528RGBA-HF"))
    )
    (comp (ref "SW1")
      (value "YD-3410")
      (footprint "SW-SMD_L3.9-W2.9-LS4.8-EH-A")
      (libsource (lib "JiangCi") (part "YD-3410"))
    )
    (comp (ref "SW2")
      (value "YD-3410")
      (footprint "SW-SMD_L3.9-W2.9-LS4.8-EH-A")
      (libsource (lib "JiangCi") (part "YD-3410"))
    )
    (comp (ref "T1")
      (value "继电器")
      (footprint "SRD-24VDC-SL-C")
      (description "5脚继电器")
      (fields (field (name "PUBLISHER") "Altium Limited"))
      (libsource (lib "JiangCi") (part "SRD-24VDC-SL-C"))
    )
    (comp (ref "T2")
      (value "testpoint")
      (footprint "testpoint")
      (description "测试点")
      (libsource (lib "JiangCi") (part "testpoint"))
    )
    (comp (ref "T3")
      (value "testpoint")
      (footprint "testpoint")
      (description "测试点")
      (libsource (lib "JiangCi") (part "testpoint"))
    )
    (comp (ref "T4")
      (value "testpoint")
      (footprint "testpoint")
      (description "测试点")
      (libsource (lib "JiangCi") (part "testpoint"))
    )
    (comp (ref "T5")
      (value "testpoint")
      (footprint "testpoint")
      (description "测试点")
      (libsource (lib "JiangCi") (part "testpoint"))
    )
    (comp (ref "T6")
      (value "testpoint")
      (footprint "testpoint")
      (description "测试点")
      (libsource (lib "JiangCi") (part "testpoint"))
    )
    (comp (ref "T7")
      (value "testpoint")
      (footprint "testpoint")
      (description "测试点")
      (libsource (lib "JiangCi") (part "testpoint"))
    )
    (comp (ref "T8")
      (value "testpoint")
      (footprint "testpoint")
      (description "测试点")
      (libsource (lib "JiangCi") (part "testpoint"))
    )
    (comp (ref "T9")
      (value "testpoint")
      (footprint "testpoint")
      (description "测试点")
      (libsource (lib "JiangCi") (part "testpoint"))
    )
    (comp (ref "T10")
      (value "testpoint")
      (footprint "testpoint")
      (description "测试点")
      (libsource (lib "JiangCi") (part "testpoint"))
    )
    (comp (ref "T11")
      (value "testpoint")
      (footprint "testpoint")
      (description "测试点")
      (libsource (lib "JiangCi") (part "testpoint"))
    )
    (comp (ref "T12")
      (value "testpoint")
      (footprint "testpoint")
      (description "测试点")
      (libsource (lib "JiangCi") (part "testpoint"))
    )
    (comp (ref "T13")
      (value "testpoint")
      (footprint "testpoint")
      (description "测试点")
      (libsource (lib "JiangCi") (part "testpoint"))
    )
    (comp (ref "T14")
      (value "testpoint")
      (footprint "testpoint")
      (description "测试点")
      (libsource (lib "JiangCi") (part "testpoint"))
    )
    (comp (ref "T15")
      (value "testpoint")
      (footprint "testpoint")
      (description "测试点")
      (libsource (lib "JiangCi") (part "testpoint"))
    )
    (comp (ref "T16")
      (value "TPS5430")
      (footprint "TPS5430DDAR")
      (description "24V-5V")
      (libsource (lib "RM2020原理图库v1.3 (1)") (part "TPS5430"))
    )
    (comp (ref "T17")
      (value "testpoint")
      (footprint "testpoint")
      (description "测试点")
      (libsource (lib "JiangCi") (part "testpoint"))
    )
    (comp (ref "T18")
      (value "testpoint")
      (footprint "testpoint")
      (description "测试点")
      (libsource (lib "JiangCi") (part "testpoint"))
    )
    (comp (ref "T19")
      (value "testpoint")
      (footprint "testpoint")
      (description "测试点")
      (libsource (lib "JiangCi") (part "testpoint"))
    )
    (comp (ref "T20")
      (value "testpoint")
      (footprint "testpoint")
      (description "测试点")
      (libsource (lib "JiangCi") (part "testpoint"))
    )
    (comp (ref "T21")
      (value "testpoint")
      (footprint "testpoint")
      (description "测试点")
      (libsource (lib "JiangCi") (part "testpoint"))
    )
    (comp (ref "U1")
      (value "LM5060")
      (footprint "VSSOP-10_L3.0-W3.0-P0.50-LS4.9-BL")
      (libsource (lib "JiangCi") (part "LM5060"))
    )
    (comp (ref "U2")
      (value "INA240A1")
      (footprint "TSSOP8")
      (description "电流放大器")
      (libsource (lib "JiangCi") (part "INA240Ax"))
    )
    (comp (ref "U3")
      (value "INA240A1")
      (footprint "TSSOP8")
      (description "电流放大器")
      (libsource (lib "JiangCi") (part "INA240Ax"))
    )
    (comp (ref "U4")
      (value "GS8591")
      (footprint "SOT-23-5_L3.0-W1.7-P0.95-LS2.8-BR")
      (libsource (lib "JiangCi") (part "GS8591"))
    )
    (comp (ref "U5")
      (value "GS8591")
      (footprint "SOT-23-5_L3.0-W1.7-P0.95-LS2.8-BR")
      (libsource (lib "JiangCi") (part "GS8591"))
    )
    (comp (ref "U6")
      (value "SLM27211")
      (footprint "SOIC-8_L4.9-W3.9-P1.27-LS6.0-BL")
      (libsource (lib "JiangCi") (part "SLM27211"))
    )
    (comp (ref "U7")
      (value "SLM27211")
      (footprint "SOIC-8_L4.9-W3.9-P1.27-LS6.0-BL")
      (libsource (lib "JiangCi") (part "SLM27211"))
    )
    (comp (ref "U8")
      (value "SN65HVD232")
      (footprint "SOP8")
      (description "CAN芯片")
      (libsource (lib "JiangCi") (part "SN65HVD232"))
    )
    (comp (ref "U9")
      (value "STM32G474CBT6")
      (footprint "LQFP-48_L7.0-W7.0-P0.50-LS9.0-BL")
      (libsource (lib "JiangCi") (part "STM32G474CBT6"))
    )
    (comp (ref "U10")
      (value "TPS54202DDCR")
      (footprint "SOT-23-6_L2.9-W1.6-P0.95-LS2.8-BL")
      (libsource (lib "JiangCi") (part "TPS54202DDCR"))
    )
    (comp (ref "U11")
      (value "AMS1117-3.3V")
      (footprint "SOT-89-3_L4.5-W2.5-P1.50-LS4.2-BR")
      (libsource (lib "JiangCi") (part "AMS1117-3.3VSOT-89"))
    )
    (comp (ref "X1")
      (value "24MHz")
      (footprint "OSC-SMD_4P-L2.0-W1.6-BL_ABRACON_AMPMAXXX")
      (libsource (lib "JiangCi") (part "AMPMAFC-25.0000T"))
    )
  )
  (nets
    (net (code "1") (name "/AD_CAP") (class "Default")
      (node (ref "R28") (pin "1") (pinfunction "1_1") (pintype "passive"))
      (node (ref "T6") (pin "1") (pinfunction "R_1") (pintype "passive"))
      (node (ref "U9") (pin "9") (pinfunction "PA1_9") (pintype "passive"))
    )
    (net (code "2") (name "/AD_IN") (class "Default")
      (node (ref "R27") (pin "1") (pinfunction "1_1") (pintype "passive"))
      (node (ref "T5") (pin "1") (pinfunction "R_1") (pintype "passive"))
      (node (ref "U9") (pin "8") (pinfunction "PA0_8") (pintype "passive"))
    )
    (net (code "3") (name "/AD_TEMP") (class "Default")
      (node (ref "C35") (pin "1") (pinfunction "1_1") (pintype "passive"))
      (node (ref "R33") (pin "2") (pinfunction "2_2") (pintype "passive"))
      (node (ref "R43") (pin "1") (pinfunction "1_1") (pintype "passive"))
      (node (ref "T7") (pin "1") (pinfunction "R_1") (pintype "passive"))
      (node (ref "U9") (pin "12") (pinfunction "PA4_12") (pintype "passive"))
    )
    (net (code "4") (name "/CAN_H") (class "Default")
      (node (ref "R36") (pin "2") (pinfunction "2_2") (pintype "passive"))
      (node (ref "R60") (pin "1") (pinfunction "1_1") (pintype "passive"))
      (node (ref "R70") (pin "1") (pinfunction "1_1") (pintype "passive"))
      (node (ref "U8") (pin "7") (pinfunction "CANH_7") (pintype "passive"))
    )
    (net (code "5") (name "/CAN_L") (class "Default")
      (node (ref "R36") (pin "1") (pinfunction "1_1") (pintype "passive"))
      (node (ref "R62") (pin "1") (pinfunction "1_1") (pintype "passive"))
      (node (ref "R72") (pin "1") (pinfunction "1_1") (pintype "passive"))
      (node (ref "U8") (pin "6") (pinfunction "CANL_6") (pintype "passive"))
    )
    (net (code "6") (name "/CAN_RX") (class "Default")
      (node (ref "U8") (pin "4") (pinfunction "RXD_4") (pintype "passive"))
      (node (ref "U9") (pin "33") (pinfunction "PA11_33") (pintype "passive"))
    )
    (net (code "7") (name "/CAN_TX") (class "Default")
      (node (ref "U8") (pin "1") (pinfunction "TXD_1") (pintype "passive"))
      (node (ref "U9") (pin "34") (pinfunction "PA12_34") (pintype "passive"))
    )
    (net (code "8") (name "/FAN") (class "Default")
      (node (ref "R74") (pin "1") (pinfunction "1_1") (pintype "passive"))
      (node (ref "U9") (pin "13") (pinfunction "PA5_13") (pintype "passive"))
    )
    (net (code "9") (name "/HOL") (class "Default")
      (node (ref "Q7") (pin "2") (pinfunction "G_2") (pintype "passive"))
      (node (ref "R38") (pin "1") (pinfunction "1_1") (pintype "passive"))
      (node (ref "T9") (pin "1") (pinfunction "R_1") (pintype "passive"))
    )
    (net (code "10") (name "/HOR") (class "Default")
      (node (ref "Q5") (pin "2") (pinfunction "G_2") (pintype "passive"))
      (node (ref "R40") (pin "1") (pinfunction "1_1") (pintype "passive"))
      (node (ref "T11") (pin "1") (pinfunction "R_1") (pintype "passive"))
    )
    (net (code "11") (name "/HRTIM1_CHA1") (class "Default")
      (node (ref "R37") (pin "2") (pinfunction "2_2") (pintype "passive"))
      (node (ref "R86") (pin "2") (pinfunction "2_2") (pintype "passive"))
      (node (ref "T8") (pin "1") (pinfunction "R_1") (pintype "passive"))
      (node (ref "U9") (pin "30") (pinfunction "PA8_30") (pintype "passive"))
    )
    (net (code "12") (name "/HRTIM1_CHA2") (class "Default")
      (node (ref "R41") (pin "2") (pinfunction "2_2") (pintype "passive"))
      (node (ref "R83") (pin "2") (pinfunction "2_2") (pintype "passive"))
      (node (ref "T12") (pin "1") (pinfunction "R_1") (pintype "passive"))
      (node (ref "U9") (pin "31") (pinfunction "PA9_31") (pintype "passive"))
    )
    (net (code "13") (name "/HRTIM1_CHD1") (class "Default")
      (node (ref "R39") (pin "2") (pinfunction "2_2") (pintype "passive"))
      (node (ref "R89") (pin "2") (pinfunction "2_2") (pintype "passive"))
      (node (ref "T10") (pin "1") (pinfunction "R_1") (pintype "passive"))
      (node (ref "U9") (pin "28") (pinfunction "PB14_28") (pintype "passive"))
    )
    (net (code "14") (name "/HRTIM1_CHD2") (class "Default")
      (node (ref "R42") (pin "2") (pinfunction "2_2") (pintype "passive"))
      (node (ref "R88") (pin "2") (pinfunction "2_2") (pintype "passive"))
      (node (ref "T13") (pin "1") (pinfunction "R_1") (pintype "passive"))
      (node (ref "U9") (pin "29") (pinfunction "PB15_29") (pintype "passive"))
    )
    (net (code "15") (name "/HSL") (class "Default")
      (node (ref "C32") (pin "1") (pinfunction "1_1") (pintype "passive"))
      (node (ref "L1") (pin "1") (pinfunction "1_1") (pintype "passive"))
      (node (ref "Q10") (pin "3") (pinfunction "3_3") (pintype "passive"))
      (node (ref "Q7") (pin "1") (pinfunction "S_1") (pintype "passive"))
      (node (ref "U6") (pin "4") (pinfunction "HS_4") (pintype "passive"))
    )
    (net (code "16") (name "/HSR") (class "Default")
      (node (ref "C33") (pin "1") (pinfunction "1_1") (pintype "passive"))
      (node (ref "L1") (pin "2") (pinfunction "2_2") (pintype "passive"))
      (node (ref "Q5") (pin "1") (pinfunction "S_1") (pintype "passive"))
      (node (ref "Q9") (pin "3") (pinfunction "3_3") (pintype "passive"))
      (node (ref "U7") (pin "4") (pinfunction "HS_4") (pintype "passive"))
    )
    (net (code "17") (name "/I2C1_SCL") (class "Default")
      (node (ref "H1") (pin "3") (pinfunction "3_3") (pintype "passive"))
      (node (ref "U9") (pin "39") (pinfunction "PA15_39") (pintype "passive"))
    )
    (net (code "18") (name "/I2C1_SDA") (class "Default")
      (node (ref "H1") (pin "4") (pinfunction "4_4") (pintype "passive"))
      (node (ref "U9") (pin "46") (pinfunction "PB9_46") (pintype "passive"))
    )
    (net (code "19") (name "/IN_EN") (class "Default")
      (node (ref "R16") (pin "2") (pinfunction "2_2") (pintype "passive"))
      (node (ref "U9") (pin "42") (pinfunction "PB5_42") (pintype "passive"))
    )
    (net (code "20") (name "/I_CAP") (class "Default")
      (node (ref "C29") (pin "2") (pinfunction "2_2") (pintype "passive"))
      (node (ref "R22") (pin "1") (pinfunction "1_1") (pintype "passive"))
      (node (ref "T4") (pin "1") (pinfunction "R_1") (pintype "passive"))
      (node (ref "U9") (pin "11") (pinfunction "PA3_11") (pintype "passive"))
    )
    (net (code "21") (name "/I_IN") (class "Default")
      (node (ref "C28") (pin "2") (pinfunction "2_2") (pintype "passive"))
      (node (ref "R21") (pin "1") (pinfunction "1_1") (pintype "passive"))
      (node (ref "T3") (pin "1") (pinfunction "R_1") (pintype "passive"))
      (node (ref "U9") (pin "10") (pinfunction "PA2_10") (pintype "passive"))
    )
    (net (code "22") (name "/LOL") (class "Default")
      (node (ref "Q10") (pin "2") (pinfunction "G_2") (pintype "passive"))
      (node (ref "R45") (pin "1") (pinfunction "1_1") (pintype "passive"))
      (node (ref "T14") (pin "1") (pinfunction "R_1") (pintype "passive"))
    )
    (net (code "23") (name "/LOR") (class "Default")
      (node (ref "Q9") (pin "2") (pinfunction "G_2") (pintype "passive"))
      (node (ref "R47") (pin "1") (pinfunction "1_1") (pintype "passive"))
      (node (ref "T15") (pin "1") (pinfunction "R_1") (pintype "passive"))
    )
    (net (code "24") (name "/MOD") (class "Default")
      (node (ref "C46") (pin "2") (pinfunction "2_2") (pintype "passive"))
      (node (ref "D9") (pin "2") (pinfunction "2_2") (pintype "passive"))
      (node (ref "R49") (pin "2") (pinfunction "2_2") (pintype "passive"))
      (node (ref "SW1") (pin "2") (pinfunction "2_2") (pintype "passive"))
      (node (ref "U9") (pin "32") (pinfunction "PA10_32") (pintype "passive"))
    )
    (net (code "25") (name "/NRST") (class "Default")
      (node (ref "C76") (pin "2") (pinfunction "2_2") (pintype "passive"))
      (node (ref "D17") (pin "2") (pinfunction "2_2") (pintype "passive"))
      (node (ref "R80") (pin "2") (pinfunction "2_2") (pintype "passive"))
      (node (ref "SW2") (pin "2") (pinfunction "2_2") (pintype "passive"))
      (node (ref "U9") (pin "7") (pinfunction "PG10-NRST_7") (pintype "passive"))
    )
    (net (code "26") (name "/OUT_EN") (class "Default")
      (node (ref "R12") (pin "2") (pinfunction "2_2") (pintype "passive"))
      (node (ref "U9") (pin "26") (pinfunction "PB12_26") (pintype "passive"))
    )
    (net (code "27") (name "/RELAY_EN") (class "Default")
      (node (ref "R2") (pin "2") (pinfunction "2_2") (pintype "passive"))
      (node (ref "U9") (pin "27") (pinfunction "PB13_27") (pintype "passive"))
    )
    (net (code "28") (name "/RGB_B") (class "Default")
      (node (ref "R61") (pin "1") (pinfunction "1_1") (pintype "passive"))
      (node (ref "U9") (pin "16") (pinfunction "PB0_16") (pintype "passive"))
    )
    (net (code "29") (name "/RGB_G") (class "Default")
      (node (ref "R57") (pin "1") (pinfunction "1_1") (pintype "passive"))
      (node (ref "U9") (pin "15") (pinfunction "PA7_15") (pintype "passive"))
    )
    (net (code "30") (name "/RGB_R") (class "Default")
      (node (ref "R51") (pin "1") (pinfunction "1_1") (pintype "passive"))
      (node (ref "U9") (pin "14") (pinfunction "PA6_14") (pintype "passive"))
    )
    (net (code "31") (name "/SWCLK") (class "Default")
      (node (ref "R81") (pin "1") (pinfunction "1_1") (pintype "passive"))
      (node (ref "U9") (pin "38") (pinfunction "PA14_38") (pintype "passive"))
    )
    (net (code "32") (name "/SWDIO") (class "Default")
      (node (ref "R79") (pin "1") (pinfunction "1_1") (pintype "passive"))
      (node (ref "U9") (pin "37") (pinfunction "PA13_37") (pintype "passive"))
    )
    (net (code "33") (name "/USART1_RX") (class "Default")
      (node (ref "R84") (pin "1") (pinfunction "1_1") (pintype "passive"))
      (node (ref "U9") (pin "44") (pinfunction "PB7_44") (pintype "passive"))
    )
    (net (code "34") (name "/USART1_TX") (class "Default")
      (node (ref "R82") (pin "1") (pinfunction "1_1") (pintype "passive"))
      (node (ref "U9") (pin "43") (pinfunction "PB6_43") (pintype "passive"))
    )
    (net (code "35") (name "/USART2_RX") (class "Default")
      (node (ref "R87") (pin "1") (pinfunction "1_1") (pintype "passive"))
      (node (ref "U9") (pin "41") (pinfunction "PB4_41") (pintype "passive"))
    )
    (net (code "36") (name "/USART2_TX") (class "Default")
      (node (ref "R85") (pin "1") (pinfunction "1_1") (pintype "passive"))
      (node (ref "U9") (pin "40") (pinfunction "PB3_40") (pintype "passive"))
    )
    (net (code "37") (name "/USART3_RX") (class "Default")
      (node (ref "R73") (pin "1") (pinfunction "1_1") (pintype "passive"))
      (node (ref "U9") (pin "25") (pinfunction "PB11_25") (pintype "passive"))
    )
    (net (code "38") (name "/USART3_TX") (class "Default")
      (node (ref "R71") (pin "1") (pinfunction "1_1") (pintype "passive"))
      (node (ref "U9") (pin "22") (pinfunction "PB10_22") (pintype "passive"))
    )
    (net (code "39") (name "3V3") (class "Default")
      (node (ref "C34") (pin "1") (pinfunction "1_1") (pintype "passive"))
      (node (ref "C36") (pin "2") (pinfunction "2_2") (pintype "passive"))
      (node (ref "C38") (pin "2") (pinfunction "2_2") (pintype "passive"))
      (node (ref "C39") (pin "1") (pinfunction "1_1") (pintype "passive"))
      (node (ref "C47") (pin "2") (pinfunction "2_2") (pintype "passive"))
      (node (ref "C54") (pin "1") (pinfunction "1_1") (pintype "passive"))
      (node (ref "C55") (pin "1") (pinfunction "1_1") (pintype "passive"))
      (node (ref "C56") (pin "1") (pinfunction "1_1") (pintype "passive"))
      (node (ref "C75") (pin "2") (pinfunction "2_2") (pintype "passive"))
      (node (ref "D18") (pin "2") (pinfunction "2_2") (pintype "passive"))
      (node (ref "FB1") (pin "1") (pinfunction "1_1") (pintype "passive"))
      (node (ref "H1") (pin "2") (pinfunction "2_2") (pintype "passive"))
      (node (ref "H6") (pin "5") (pinfunction "5_5") (pintype "passive"))
      (node (ref "H7") (pin "2") (pinfunction "2_2") (pintype "passive"))
      (node (ref "R49") (pin "1") (pinfunction "1_1") (pintype "passive"))
      (node (ref "R77") (pin "2") (pinfunction "2_2") (pintype "passive"))
      (node (ref "R80") (pin "1") (pinfunction "1_1") (pintype "passive"))
      (node (ref "RGB1") (pin "2") (pinfunction "A+_2") (pintype "passive"))
      (node (ref "U8") (pin "3") (pinfunction "VCC_3") (pintype "passive"))
      (node (ref "U9") (pin "1") (pinfunction "VBAT_1") (pintype "passive"))
      (node (ref "U9") (pin "24") (pinfunction "VDD_24") (pintype "passive"))
      (node (ref "U9") (pin "36") (pinfunction "VDD_36") (pintype "passive"))
      (node (ref "U9") (pin "48") (pinfunction "VDD_48") (pintype "passive"))
      (node (ref "X1") (pin "4") (pinfunction "VDD_4") (pintype "passive"))
    )
    (net (code "40") (name "3V3_M") (class "Default")
      (node (ref "C70") (pin "1") (pinfunction "1_1") (pintype "passive"))
      (node (ref "C73") (pin "2") (pinfunction "2_2") (pintype "passive"))
      (node (ref "R77") (pin "1") (pinfunction "1_1") (pintype "passive"))
      (node (ref "R78") (pin "2") (pinfunction "2_2") (pintype "passive"))
      (node (ref "T20") (pin "1") (pinfunction "R_1") (pintype "passive"))
      (node (ref "U11") (pin "2") (pinfunction "VOUT_2") (pintype "passive"))
    )
    (net (code "41") (name "5V") (class "Default")
      (node (ref "C62") (pin "2") (pinfunction "2_2") (pintype "passive"))
      (node (ref "C71") (pin "2") (pinfunction "2_2") (pintype "passive"))
      (node (ref "C72") (pin "2") (pinfunction "2_2") (pintype "passive"))
      (node (ref "H4") (pin "4") (pinfunction "4_4") (pintype "passive"))
      (node (ref "R75") (pin "2") (pinfunction "2_2") (pintype "passive"))
      (node (ref "U11") (pin "3") (pinfunction "VIN_3") (pintype "passive"))
    )
    (net (code "42") (name "5V_M") (class "Default")
      (node (ref "C57") (pin "2") (pinfunction "2_2") (pintype "passive"))
      (node (ref "C58") (pin "2") (pinfunction "2_2") (pintype "passive"))
      (node (ref "L3") (pin "2") (pinfunction "2_2") (pintype "passive"))
      (node (ref "R65") (pin "2") (pinfunction "2_2") (pintype "passive"))
      (node (ref "R66") (pin "2") (pinfunction "2_2") (pintype "passive"))
      (node (ref "R75") (pin "1") (pinfunction "1_1") (pintype "passive"))
      (node (ref "T19") (pin "1") (pinfunction "R_1") (pintype "passive"))
    )
    (net (code "43") (name "12V") (class "Default")
      (node (ref "C30") (pin "2") (pinfunction "2_2") (pintype "passive"))
      (node (ref "C31") (pin "2") (pinfunction "2_2") (pintype "passive"))
      (node (ref "C59") (pin "2") (pinfunction "2_2") (pintype "passive"))
      (node (ref "C60") (pin "2") (pinfunction "2_2") (pintype "passive"))
      (node (ref "C65") (pin "1") (pinfunction "1_1") (pintype "passive"))
      (node (ref "C74") (pin "2") (pinfunction "2_2") (pintype "passive"))
      (node (ref "H3") (pin "2") (pinfunction "2_2") (pintype "passive"))
      (node (ref "H7") (pin "1") (pinfunction "1_1") (pintype "passive"))
      (node (ref "R64") (pin "2") (pinfunction "2_2") (pintype "passive"))
      (node (ref "R69") (pin "2") (pinfunction "2_2") (pintype "passive"))
      (node (ref "U10") (pin "3") (pinfunction "VIN_3") (pintype "passive"))
      (node (ref "U6") (pin "1") (pinfunction "VDD_1") (pintype "passive"))
      (node (ref "U7") (pin "1") (pinfunction "VDD_1") (pintype "passive"))
    )
    (net (code "44") (name "12V_M") (class "Default")
      (node (ref "F1") (pin "2") (pinfunction "2_2") (pintype "passive"))
      (node (ref "R53") (pin "2") (pinfunction "2_2") (pintype "passive"))
      (node (ref "R69") (pin "1") (pinfunction "1_1") (pintype "passive"))
      (node (ref "T18") (pin "1") (pinfunction "R_1") (pintype "passive"))
    )
    (net (code "45") (name "AGND") (class "Default")
      (node (ref "C22") (pin "1") (pinfunction "1_1") (pintype "passive"))
      (node (ref "C23") (pin "1") (pinfunction "1_1") (pintype "passive"))
      (node (ref "C24") (pin "1") (pinfunction "1_1") (pintype "passive"))
      (node (ref "C25") (pin "1") (pinfunction "1_1") (pintype "passive"))
      (node (ref "C28") (pin "1") (pinfunction "1_1") (pintype "passive"))
      (node (ref "C29") (pin "1") (pinfunction "1_1") (pintype "passive"))
      (node (ref "C35") (pin "2") (pinfunction "2_2") (pintype "passive"))
      (node (ref "C49") (pin "2") (pinfunction "2_2") (pintype "passive"))
      (node (ref "C50") (pin "2") (pinfunction "2_2") (pintype "passive"))
      (node (ref "C51") (pin "2") (pinfunction "2_2") (pintype "passive"))
      (node (ref "C61") (pin "2") (pinfunction "2_2") (pintype "passive"))
      (node (ref "C63") (pin "1") (pinfunction "1_1") (pintype "passive"))
      (node (ref "C64") (pin "1") (pinfunction "1_1") (pintype "passive"))
      (node (ref "FB2") (pin "2") (pinfunction "2_2") (pintype "passive"))
      (node (ref "R17") (pin "1") (pinfunction "1_1") (pintype "passive"))
      (node (ref "R18") (pin "1") (pinfunction "1_1") (pintype "passive"))
      (node (ref "R29") (pin "2") (pinfunction "2_2") (pintype "passive"))
      (node (ref "R30") (pin "2") (pinfunction "2_2") (pintype "passive"))
      (node (ref "R43") (pin "2") (pinfunction "2_2") (pintype "passive"))
      (node (ref "U2") (pin "4") (pinfunction "GND_4") (pintype "passive"))
      (node (ref "U2") (pin "6") (pinfunction "REF2_6") (pintype "passive"))
      (node (ref "U2") (pin "7") (pinfunction "REF1_7") (pintype "passive"))
      (node (ref "U3") (pin "4") (pinfunction "GND_4") (pintype "passive"))
      (node (ref "U3") (pin "7") (pinfunction "REF1_7") (pintype "passive"))
      (node (ref "U4") (pin "2") (pinfunction "V-_2") (pintype "passive"))
      (node (ref "U5") (pin "2") (pinfunction "V-_2") (pintype "passive"))
      (node (ref "U9") (pin "19") (pinfunction "VSSA_19") (pintype "passive"))
    )
    (net (code "46") (name "AVDD") (class "Default")
      (node (ref "C22") (pin "2") (pinfunction "2_2") (pintype "passive"))
      (node (ref "C23") (pin "2") (pinfunction "2_2") (pintype "passive"))
      (node (ref "C24") (pin "2") (pinfunction "2_2") (pintype "passive"))
      (node (ref "C25") (pin "2") (pinfunction "2_2") (pintype "passive"))
      (node (ref "C49") (pin "1") (pinfunction "1_1") (pintype "passive"))
      (node (ref "C50") (pin "1") (pinfunction "1_1") (pintype "passive"))
      (node (ref "C51") (pin "1") (pinfunction "1_1") (pintype "passive"))
      (node (ref "C61") (pin "1") (pinfunction "1_1") (pintype "passive"))
      (node (ref "C63") (pin "2") (pinfunction "2_2") (pintype "passive"))
      (node (ref "C64") (pin "2") (pinfunction "2_2") (pintype "passive"))
      (node (ref "FB1") (pin "2") (pinfunction "2_2") (pintype "passive"))
      (node (ref "R33") (pin "1") (pinfunction "1_1") (pintype "passive"))
      (node (ref "T17") (pin "1") (pinfunction "R_1") (pintype "passive"))
      (node (ref "U2") (pin "5") (pinfunction "VS_5") (pintype "passive"))
      (node (ref "U3") (pin "5") (pinfunction "VS_5") (pintype "passive"))
      (node (ref "U3") (pin "6") (pinfunction "REF2_6") (pintype "passive"))
      (node (ref "U4") (pin "5") (pinfunction "V+_5") (pintype "passive"))
      (node (ref "U5") (pin "5") (pinfunction "V+_5") (pintype "passive"))
      (node (ref "U9") (pin "20") (pinfunction "VREF+_20") (pintype "passive"))
      (node (ref "U9") (pin "21") (pinfunction "VDDA_21") (pintype "passive"))
    )
    (net (code "47") (name "GND") (class "Default")
      (node (ref "C1") (pin "1") (pinfunction "1_1") (pintype "passive"))
      (node (ref "C30") (pin "1") (pinfunction "1_1") (pintype "passive"))
      (node (ref "C31") (pin "1") (pinfunction "1_1") (pintype "passive"))
      (node (ref "C34") (pin "2") (pinfunction "2_2") (pintype "passive"))
      (node (ref "C36") (pin "1") (pinfunction "1_1") (pintype "passive"))
      (node (ref "C38") (pin "1") (pinfunction "1_1") (pintype "passive"))
      (node (ref "C39") (pin "2") (pinfunction "2_2") (pintype "passive"))
      (node (ref "C40") (pin "1") (pinfunction "1_1") (pintype "passive"))
      (node (ref "C41") (pin "1") (pinfunction "1_1") (pintype "passive"))
      (node (ref "C42") (pin "1") (pinfunction "1_1") (pintype "passive"))
      (node (ref "C43") (pin "1") (pinfunction "1_1") (pintype "passive"))
      (node (ref "C44") (pin "1") (pinfunction "1_1") (pintype "passive"))
      (node (ref "C45") (pin "1") (pinfunction "1_1") (pintype "passive"))
      (node (ref "C46") (pin "1") (pinfunction "1_1") (pintype "passive"))
      (node (ref "C47") (pin "1") (pinfunction "1_1") (pintype "passive"))
      (node (ref "C48") (pin "1") (pinfunction "1_1") (pintype "passive"))
      (node (ref "C52") (pin "1") (pinfunction "1_1") (pintype "passive"))
      (node (ref "C54") (pin "2") (pinfunction "2_2") (pintype "passive"))
      (node (ref "C55") (pin "2") (pinfunction "2_2") (pintype "passive"))
      (node (ref "C56") (pin "2") (pinfunction "2_2") (pintype "passive"))
      (node (ref "C57") (pin "1") (pinfunction "1_1") (pintype "passive"))
      (node (ref "C58") (pin "1") (pinfunction "1_1") (pintype "passive"))
      (node (ref "C59") (pin "1") (pinfunction "1_1") (pintype "passive"))
      (node (ref "C60") (pin "1") (pinfunction "1_1") (pintype "passive"))
      (node (ref "C62") (pin "1") (pinfunction "1_1") (pintype "passive"))
      (node (ref "C65") (pin "2") (pinfunction "2_2") (pintype "passive"))
      (node (ref "C66") (pin "1") (pinfunction "1_1") (pintype "passive"))
      (node (ref "C67") (pin "1") (pinfunction "1_1") (pintype "passive"))
      (node (ref "C68") (pin "2") (pinfunction "2_2") (pintype "passive"))
      (node (ref "C69") (pin "1") (pinfunction "1_1") (pintype "passive"))
      (node (ref "C70") (pin "2") (pinfunction "2_2") (pintype "passive"))
      (node (ref "C71") (pin "1") (pinfunction "1_1") (pintype "passive"))
      (node (ref "C72") (pin "1") (pinfunction "1_1") (pintype "passive"))
      (node (ref "C73") (pin "1") (pinfunction "1_1") (pintype "passive"))
      (node (ref "C74") (pin "1") (pinfunction "1_1") (pintype "passive"))
      (node (ref "C75") (pin "1") (pinfunction "1_1") (pintype "passive"))
      (node (ref "C76") (pin "1") (pinfunction "1_1") (pintype "passive"))
      (node (ref "C77") (pin "2") (pinfunction "2_2") (pintype "passive"))
      (node (ref "C78") (pin "1") (pinfunction "1_1") (pintype "passive"))
      (node (ref "C79") (pin "2") (pinfunction "2_2") (pintype "passive"))
      (node (ref "C80") (pin "1") (pinfunction "1_1") (pintype "passive"))
      (node (ref "D10") (pin "1") (pinfunction "A_1") (pintype "passive"))
      (node (ref "D11") (pin "2") (pinfunction "2_2") (pintype "passive"))
      (node (ref "D12") (pin "1") (pinfunction "1_1") (pintype "passive"))
      (node (ref "D13") (pin "2") (pinfunction "2_2") (pintype "passive"))
      (node (ref "D14") (pin "1") (pinfunction "1_1") (pintype "passive"))
      (node (ref "D15") (pin "1") (pinfunction "1_1") (pintype "passive"))
      (node (ref "D16") (pin "1") (pinfunction "1_1") (pintype "passive"))
      (node (ref "D17") (pin "1") (pinfunction "1_1") (pintype "passive"))
      (node (ref "D18") (pin "1") (pinfunction "1_1") (pintype "passive"))
      (node (ref "D19") (pin "1") (pinfunction "1_1") (pintype "passive"))
      (node (ref "D20") (pin "1") (pinfunction "1_1") (pintype "passive"))
      (node (ref "D21") (pin "1") (pinfunction "1_1") (pintype "passive"))
      (node (ref "D22") (pin "1") (pinfunction "1_1") (pintype "passive"))
      (node (ref "D9") (pin "1") (pinfunction "1_1") (pintype "passive"))
      (node (ref "FB2") (pin "1") (pinfunction "1_1") (pintype "passive"))
      (node (ref "FB3") (pin "1") (pinfunction "1_1") (pintype "passive"))
      (node (ref "H1") (pin "1") (pinfunction "1_1") (pintype "passive"))
      (node (ref "H2") (pin "3") (pinfunction "3_3") (pintype "passive"))
      (node (ref "H2") (pin "4") (pinfunction "4_4") (pintype "passive"))
      (node (ref "H4") (pin "1") (pinfunction "1_1") (pintype "passive"))
      (node (ref "H4") (pin "5") (pinfunction "5_5") (pintype "passive"))
      (node (ref "H4") (pin "6") (pinfunction "6_6") (pintype "passive"))
      (node (ref "H5") (pin "3") (pinfunction "3_3") (pintype "passive"))
      (node (ref "H5") (pin "4") (pinfunction "4_4") (pintype "passive"))
      (node (ref "H6") (pin "4") (pinfunction "4_4") (pintype "passive"))
      (node (ref "H6") (pin "6") (pinfunction "6_6") (pintype "passive"))
      (node (ref "H6") (pin "7") (pinfunction "7_7") (pintype "passive"))
      (node (ref "H7") (pin "5") (pinfunction "5_5") (pintype "passive"))
      (node (ref "H7") (pin "6") (pinfunction "6_6") (pintype "passive"))
      (node (ref "H7") (pin "7") (pinfunction "7_7") (pintype "passive"))
      (node (ref "H8") (pin "1") (pinfunction "1_1") (pintype "passive"))
      (node (ref "H8") (pin "6") (pinfunction "6_6") (pintype "passive"))
      (node (ref "H8") (pin "7") (pinfunction "7_7") (pintype "passive"))
      (node (ref "H9") (pin "1") (pinfunction "1_1") (pintype "passive"))
      (node (ref "H9") (pin "4") (pinfunction "4_4") (pintype "passive"))
      (node (ref "H9") (pin "5") (pinfunction "5_5") (pintype "passive"))
      (node (ref "LED1") (pin "1") (pinfunction "K_1") (pintype "passive"))
      (node (ref "LED2") (pin "1") (pinfunction "K_1") (pintype "passive"))
      (node (ref "LED3") (pin "1") (pinfunction "K_1") (pintype "passive"))
      (node (ref "Q11") (pin "2") (pinfunction "S_2") (pintype "passive"))
      (node (ref "Q12") (pin "2") (pinfunction "S_2") (pintype "passive"))
      (node (ref "Q13") (pin "2") (pinfunction "S_2") (pintype "passive"))
      (node (ref "Q14") (pin "2") (pinfunction "S_2") (pintype "passive"))
      (node (ref "R34") (pin "1") (pinfunction "1_1") (pintype "passive"))
      (node (ref "R35") (pin "1") (pinfunction "1_1") (pintype "passive"))
      (node (ref "R44") (pin "2") (pinfunction "2_2") (pintype "passive"))
      (node (ref "R46") (pin "2") (pinfunction "2_2") (pintype "passive"))
      (node (ref "R50") (pin "1") (pinfunction "1_1") (pintype "passive"))
      (node (ref "R54") (pin "2") (pinfunction "2_2") (pintype "passive"))
      (node (ref "R56") (pin "1") (pinfunction "1_1") (pintype "passive"))
      (node (ref "R58") (pin "2") (pinfunction "2_2") (pintype "passive"))
      (node (ref "R63") (pin "2") (pinfunction "2_2") (pintype "passive"))
      (node (ref "R67") (pin "1") (pinfunction "1_1") (pintype "passive"))
      (node (ref "R68") (pin "1") (pinfunction "1_1") (pintype "passive"))
      (node (ref "R76") (pin "2") (pinfunction "2_2") (pintype "passive"))
      (node (ref "SW1") (pin "1") (pinfunction "1_1") (pintype "passive"))
      (node (ref "SW2") (pin "1") (pinfunction "1_1") (pintype "passive"))
      (node (ref "T16") (pin "6") (pinfunction "GND_6") (pintype "passive"))
      (node (ref "T16") (pin "9") (pinfunction "PADS_9") (pintype "passive"))
      (node (ref "T21") (pin "1") (pinfunction "R_1") (pintype "passive"))
      (node (ref "U10") (pin "1") (pinfunction "GND_1") (pintype "passive"))
      (node (ref "U11") (pin "1") (pinfunction "GND_1") (pintype "passive"))
      (node (ref "U6") (pin "7") (pinfunction "VSS_7") (pintype "passive"))
      (node (ref "U7") (pin "7") (pinfunction "VSS_7") (pintype "passive"))
      (node (ref "U8") (pin "2") (pinfunction "GND_2") (pintype "passive"))
      (node (ref "U9") (pin "23") (pinfunction "VSS_23") (pintype "passive"))
      (node (ref "U9") (pin "35") (pinfunction "VSS_35") (pintype "passive"))
      (node (ref "U9") (pin "47") (pinfunction "VSS_47") (pintype "passive"))
      (node (ref "X1") (pin "2") (pinfunction "GND_2") (pintype "passive"))
    )
    (net (code "48") (name "Net-(C43-Pad2)") (class "Default")
      (node (ref "C43") (pin "2") (pinfunction "2_2") (pintype "passive"))
      (node (ref "C44") (pin "2") (pinfunction "2_2") (pintype "passive"))
      (node (ref "C45") (pin "2") (pinfunction "2_2") (pintype "passive"))
      (node (ref "F1") (pin "1") (pinfunction "1_1") (pintype "passive"))
      (node (ref "L2") (pin "2") (pinfunction "2_2") (pintype "passive"))
      (node (ref "R52") (pin "2") (pinfunction "2_2") (pintype "passive"))
    )
    (net (code "49") (name "Net-(C48-Pad2)") (class "Default")
      (node (ref "C48") (pin "2") (pinfunction "2_2") (pintype "passive"))
      (node (ref "D11") (pin "1") (pinfunction "1_1") (pintype "passive"))
      (node (ref "H2") (pin "2") (pinfunction "2_2") (pintype "passive"))
      (node (ref "R60") (pin "2") (pinfunction "2_2") (pintype "passive"))
    )
    (net (code "50") (name "Net-(C52-Pad2)") (class "Default")
      (node (ref "C52") (pin "2") (pinfunction "2_2") (pintype "passive"))
      (node (ref "D12") (pin "2") (pinfunction "2_2") (pintype "passive"))
      (node (ref "H2") (pin "1") (pinfunction "1_1") (pintype "passive"))
      (node (ref "R62") (pin "2") (pinfunction "2_2") (pintype "passive"))
    )
    (net (code "51") (name "Net-(C66-Pad2)") (class "Default")
      (node (ref "C66") (pin "2") (pinfunction "2_2") (pintype "passive"))
      (node (ref "D13") (pin "1") (pinfunction "1_1") (pintype "passive"))
      (node (ref "H5") (pin "2") (pinfunction "2_2") (pintype "passive"))
      (node (ref "R70") (pin "2") (pinfunction "2_2") (pintype "passive"))
    )
    (net (code "52") (name "Net-(C67-Pad2)") (class "Default")
      (node (ref "C67") (pin "2") (pinfunction "2_2") (pintype "passive"))
      (node (ref "D14") (pin "2") (pinfunction "2_2") (pintype "passive"))
      (node (ref "H5") (pin "1") (pinfunction "1_1") (pintype "passive"))
      (node (ref "R72") (pin "2") (pinfunction "2_2") (pintype "passive"))
    )
    (net (code "53") (name "Net-(C68-Pad1)") (class "Default")
      (node (ref "C68") (pin "1") (pinfunction "1_1") (pintype "passive"))
      (node (ref "D15") (pin "2") (pinfunction "2_2") (pintype "passive"))
      (node (ref "H4") (pin "2") (pinfunction "2_2") (pintype "passive"))
      (node (ref "R73") (pin "2") (pinfunction "2_2") (pintype "passive"))
    )
    (net (code "54") (name "Net-(C69-Pad2)") (class "Default")
      (node (ref "C69") (pin "2") (pinfunction "2_2") (pintype "passive"))
      (node (ref "D16") (pin "2") (pinfunction "2_2") (pintype "passive"))
      (node (ref "H4") (pin "3") (pinfunction "3_3") (pintype "passive"))
      (node (ref "R71") (pin "2") (pinfunction "2_2") (pintype "passive"))
    )
    (net (code "55") (name "Net-(C77-Pad1)") (class "Default")
      (node (ref "C77") (pin "1") (pinfunction "1_1") (pintype "passive"))
      (node (ref "D19") (pin "2") (pinfunction "2_2") (pintype "passive"))
      (node (ref "H9") (pin "2") (pinfunction "2_2") (pintype "passive"))
      (node (ref "R84") (pin "2") (pinfunction "2_2") (pintype "passive"))
    )
    (net (code "56") (name "Net-(C78-Pad2)") (class "Default")
      (node (ref "C78") (pin "2") (pinfunction "2_2") (pintype "passive"))
      (node (ref "D20") (pin "2") (pinfunction "2_2") (pintype "passive"))
      (node (ref "H9") (pin "3") (pinfunction "3_3") (pintype "passive"))
      (node (ref "R82") (pin "2") (pinfunction "2_2") (pintype "passive"))
    )
    (net (code "57") (name "Net-(C79-Pad1)") (class "Default")
      (node (ref "C79") (pin "1") (pinfunction "1_1") (pintype "passive"))
      (node (ref "D21") (pin "2") (pinfunction "2_2") (pintype "passive"))
      (node (ref "H7") (pin "4") (pinfunction "4_4") (pintype "passive"))
      (node (ref "R87") (pin "2") (pinfunction "2_2") (pintype "passive"))
    )
    (net (code "58") (name "Net-(C80-Pad2)") (class "Default")
      (node (ref "C80") (pin "2") (pinfunction "2_2") (pintype "passive"))
      (node (ref "D22") (pin "2") (pinfunction "2_2") (pintype "passive"))
      (node (ref "H7") (pin "3") (pinfunction "3_3") (pintype "passive"))
      (node (ref "R85") (pin "2") (pinfunction "2_2") (pintype "passive"))
    )
    (net (code "59") (name "Net-(D1-A)") (class "Default")
      (node (ref "D1") (pin "2") (pinfunction "A_2") (pintype "passive"))
      (node (ref "Q1") (pin "3") (pinfunction "C_3") (pintype "passive"))
      (node (ref "T1") (pin "1") (pinfunction "1_1") (pintype "passive"))
    )
    (net (code "60") (name "Net-(D2-A)") (class "Default")
      (node (ref "D2") (pin "2") (pinfunction "A_2") (pintype "passive"))
      (node (ref "Q2") (pin "2") (pinfunction "G_2") (pintype "passive"))
      (node (ref "Q3") (pin "2") (pinfunction "G_2") (pintype "passive"))
      (node (ref "Q6") (pin "3") (pinfunction "C_3") (pintype "passive"))
      (node (ref "R8") (pin "2") (pinfunction "2_2") (pintype "passive"))
    )
    (net (code "61") (name "Net-(D2-C)") (class "Default")
      (node (ref "D2") (pin "1") (pinfunction "C_1") (pintype "passive"))
      (node (ref "R8") (pin "1") (pinfunction "1_1") (pintype "passive"))
      (node (ref "U1") (pin "10") (pinfunction "GATE_10") (pintype "passive"))
    )
    (net (code "62") (name "Net-(D3-A)") (class "Default")
      (node (ref "D3") (pin "1") (pinfunction "A_1") (pintype "passive"))
      (node (ref "Q4") (pin "2") (pinfunction "G_2") (pintype "passive"))
      (node (ref "R5") (pin "1") (pinfunction "1_1") (pintype "passive"))
      (node (ref "R9") (pin "2") (pinfunction "2_2") (pintype "passive"))
      (node (ref "T2") (pin "1") (pinfunction "R_1") (pintype "passive"))
    )
    (net (code "63") (name "Net-(D3-K)") (class "Default")
      (node (ref "D3") (pin "2") (pinfunction "K_2") (pintype "passive"))
      (node (ref "Q4") (pin "1") (pinfunction "S_1") (pintype "passive"))
      (node (ref "R5") (pin "2") (pinfunction "2_2") (pintype "passive"))
      (node (ref "T1") (pin "3") (pinfunction "3_3") (pintype "passive"))
    )
    (net (code "64") (name "Net-(D4-C)") (class "Default")
      (node (ref "C1") (pin "2") (pinfunction "2_2") (pintype "passive"))
      (node (ref "D4") (pin "1") (pinfunction "C_1") (pintype "passive"))
      (node (ref "U1") (pin "2") (pinfunction "VIN_2") (pintype "passive"))
    )
    (net (code "65") (name "Net-(D5-A)") (class "Default")
      (node (ref "D5") (pin "2") (pinfunction "A_2") (pintype "passive"))
      (node (ref "Q2") (pin "1") (pinfunction "S_1") (pintype "passive"))
      (node (ref "Q3") (pin "1") (pinfunction "S_1") (pintype "passive"))
      (node (ref "Q6") (pin "2") (pinfunction "E_2") (pintype "passive"))
    )
    (net (code "66") (name "Net-(D5-C)") (class "Default")
      (node (ref "D5") (pin "1") (pinfunction "C_1") (pintype "passive"))
      (node (ref "Q6") (pin "1") (pinfunction "B_1") (pintype "passive"))
      (node (ref "R14") (pin "2") (pinfunction "2_2") (pintype "passive"))
    )
    (net (code "67") (name "Net-(D8-K)") (class "Default")
      (node (ref "C18") (pin "2") (pinfunction "2_2") (pintype "passive"))
      (node (ref "C19") (pin "2") (pinfunction "2_2") (pintype "passive"))
      (node (ref "D8") (pin "2") (pinfunction "K_2") (pintype "passive"))
      (node (ref "P3") (pin "1") (pinfunction "1_1") (pintype "passive"))
      (node (ref "Q4") (pin "3") (pinfunction "D_3") (pintype "passive"))
    )
    (net (code "68") (name "Net-(D10-K)") (class "Default")
      (node (ref "C37") (pin "2") (pinfunction "2_2") (pintype "passive"))
      (node (ref "D10") (pin "2") (pinfunction "K_2") (pintype "passive"))
      (node (ref "L2") (pin "1") (pinfunction "1_1") (pintype "passive"))
      (node (ref "T16") (pin "8") (pinfunction "PH_8") (pintype "passive"))
    )
    (net (code "69") (name "Net-(H6-Pad1)") (class "Default")
      (node (ref "H6") (pin "1") (pinfunction "1_1") (pintype "passive"))
      (node (ref "R79") (pin "2") (pinfunction "2_2") (pintype "passive"))
    )
    (net (code "70") (name "Net-(H6-Pad2)") (class "Default")
      (node (ref "H6") (pin "2") (pinfunction "2_2") (pintype "passive"))
      (node (ref "R81") (pin "2") (pinfunction "2_2") (pintype "passive"))
    )
    (net (code "71") (name "Net-(H8-Pad2)") (class "Default")
      (node (ref "H8") (pin "2") (pinfunction "2_2") (pintype "passive"))
      (node (ref "R89") (pin "1") (pinfunction "1_1") (pintype "passive"))
    )
    (net (code "72") (name "Net-(H8-Pad3)") (class "Default")
      (node (ref "H8") (pin "3") (pinfunction "3_3") (pintype "passive"))
      (node (ref "R88") (pin "1") (pinfunction "1_1") (pintype "passive"))
    )
    (net (code "73") (name "Net-(H8-Pad4)") (class "Default")
      (node (ref "H8") (pin "4") (pinfunction "4_4") (pintype "passive"))
      (node (ref "R86") (pin "1") (pinfunction "1_1") (pintype "passive"))
    )
    (net (code "74") (name "Net-(H8-Pad5)") (class "Default")
      (node (ref "H8") (pin "5") (pinfunction "5_5") (pintype "passive"))
      (node (ref "R83") (pin "1") (pinfunction "1_1") (pintype "passive"))
    )
    (net (code "75") (name "Net-(LED1-A)") (class "Default")
      (node (ref "LED1") (pin "2") (pinfunction "A_2") (pintype "passive"))
      (node (ref "R53") (pin "1") (pinfunction "1_1") (pintype "passive"))
    )
    (net (code "76") (name "Net-(LED2-A)") (class "Default")
      (node (ref "LED2") (pin "2") (pinfunction "A_2") (pintype "passive"))
      (node (ref "R66") (pin "1") (pinfunction "1_1") (pintype "passive"))
    )
    (net (code "77") (name "Net-(LED3-A)") (class "Default")
      (node (ref "LED3") (pin "2") (pinfunction "A_2") (pintype "passive"))
      (node (ref "R78") (pin "1") (pinfunction "1_1") (pintype "passive"))
    )
    (net (code "78") (name "Net-(Q1-B)") (class "Default")
      (node (ref "Q1") (pin "1") (pinfunction "B_1") (pintype "passive"))
      (node (ref "R2") (pin "1") (pinfunction "1_1") (pintype "passive"))
      (node (ref "R3") (pin "2") (pinfunction "2_2") (pintype "passive"))
    )
    (net (code "79") (name "Net-(Q3-D)") (class "Default")
      (node (ref "C2") (pin "2") (pinfunction "2_2") (pintype "passive"))
      (node (ref "C3") (pin "2") (pinfunction "2_2") (pintype "passive"))
      (node (ref "C4") (pin "2") (pinfunction "2_2") (pintype "passive"))
      (node (ref "C5") (pin "2") (pinfunction "2_2") (pintype "passive"))
      (node (ref "C6") (pin "2") (pinfunction "2_2") (pintype "passive"))
      (node (ref "C7") (pin "2") (pinfunction "2_2") (pintype "passive"))
      (node (ref "C8") (pin "2") (pinfunction "2_2") (pintype "passive"))
      (node (ref "C9") (pin "2") (pinfunction "2_2") (pintype "passive"))
      (node (ref "Q3") (pin "3") (pinfunction "D_3") (pintype "passive"))
      (node (ref "Q7") (pin "3") (pinfunction "3_3") (pintype "passive"))
      (node (ref "R11") (pin "2") (pinfunction "2_2") (pintype "passive"))
      (node (ref "T1") (pin "4") (pinfunction "4_4") (pintype "passive"))
    )
    (net (code "80") (name "Net-(Q8-B)") (class "Default")
      (node (ref "Q8") (pin "1") (pinfunction "B_1") (pintype "passive"))
      (node (ref "R12") (pin "1") (pinfunction "1_1") (pintype "passive"))
      (node (ref "R15") (pin "2") (pinfunction "2_2") (pintype "passive"))
    )
    (net (code "81") (name "Net-(Q8-C)") (class "Default")
      (node (ref "Q8") (pin "3") (pinfunction "C_3") (pintype "passive"))
      (node (ref "R9") (pin "1") (pinfunction "1_1") (pintype "passive"))
    )
    (net (code "82") (name "Net-(Q11-D)") (class "Default")
      (node (ref "Q11") (pin "3") (pinfunction "D_3") (pintype "passive"))
      (node (ref "R48") (pin "1") (pinfunction "1_1") (pintype "passive"))
    )
    (net (code "83") (name "Net-(Q11-G)") (class "Default")
      (node (ref "Q11") (pin "1") (pinfunction "G_1") (pintype "passive"))
      (node (ref "R51") (pin "2") (pinfunction "2_2") (pintype "passive"))
      (node (ref "R54") (pin "1") (pinfunction "1_1") (pintype "passive"))
    )
    (net (code "84") (name "Net-(Q12-D)") (class "Default")
      (node (ref "Q12") (pin "3") (pinfunction "D_3") (pintype "passive"))
      (node (ref "R55") (pin "1") (pinfunction "1_1") (pintype "passive"))
    )
    (net (code "85") (name "Net-(Q12-G)") (class "Default")
      (node (ref "Q12") (pin "1") (pinfunction "G_1") (pintype "passive"))
      (node (ref "R57") (pin "2") (pinfunction "2_2") (pintype "passive"))
      (node (ref "R58") (pin "1") (pinfunction "1_1") (pintype "passive"))
    )
    (net (code "86") (name "Net-(Q13-D)") (class "Default")
      (node (ref "Q13") (pin "3") (pinfunction "D_3") (pintype "passive"))
      (node (ref "R59") (pin "1") (pinfunction "1_1") (pintype "passive"))
    )
    (net (code "87") (name "Net-(Q13-G)") (class "Default")
      (node (ref "Q13") (pin "1") (pinfunction "G_1") (pintype "passive"))
      (node (ref "R61") (pin "2") (pinfunction "2_2") (pintype "passive"))
      (node (ref "R63") (pin "1") (pinfunction "1_1") (pintype "passive"))
    )
    (net (code "88") (name "Net-(Q14-D)") (class "Default")
      (node (ref "H3") (pin "1") (pinfunction "1_1") (pintype "passive"))
      (node (ref "Q14") (pin "3") (pinfunction "D_3") (pintype "passive"))
    )
    (net (code "89") (name "Net-(Q14-G)") (class "Default")
      (node (ref "Q14") (pin "1") (pinfunction "G_1") (pintype "passive"))
      (node (ref "R74") (pin "2") (pinfunction "2_2") (pintype "passive"))
      (node (ref "R76") (pin "1") (pinfunction "1_1") (pintype "passive"))
    )
    (net (code "90") (name "Net-(RGB1-B-)") (class "Default")
      (node (ref "R59") (pin "2") (pinfunction "2_2") (pintype "passive"))
      (node (ref "RGB1") (pin "3") (pinfunction "B-_3") (pintype "passive"))
    )
    (net (code "91") (name "Net-(RGB1-G-)") (class "Default")
      (node (ref "R55") (pin "2") (pinfunction "2_2") (pintype "passive"))
      (node (ref "RGB1") (pin "4") (pinfunction "G-_4") (pintype "passive"))
    )
    (net (code "92") (name "Net-(RGB1-R-)") (class "Default")
      (node (ref "R48") (pin "2") (pinfunction "2_2") (pintype "passive"))
      (node (ref "RGB1") (pin "1") (pinfunction "R-_1") (pintype "passive"))
    )
    (net (code "93") (name "Net-(T16-BOOT)") (class "Default")
      (node (ref "C37") (pin "1") (pinfunction "1_1") (pintype "passive"))
      (node (ref "T16") (pin "1") (pinfunction "BOOT_1") (pintype "passive"))
    )
    (net (code "94") (name "Net-(T16-REF)") (class "Default")
      (node (ref "R52") (pin "1") (pinfunction "1_1") (pintype "passive"))
      (node (ref "R56") (pin "2") (pinfunction "2_2") (pintype "passive"))
      (node (ref "T16") (pin "4") (pinfunction "REF_4") (pintype "passive"))
    )
    (net (code "95") (name "Net-(U1-EN)") (class "Default")
      (node (ref "R16") (pin "1") (pinfunction "1_1") (pintype "passive"))
      (node (ref "U1") (pin "5") (pinfunction "EN_5") (pintype "passive"))
    )
    (net (code "96") (name "Net-(U1-OUT)") (class "Default")
      (node (ref "R11") (pin "1") (pinfunction "1_1") (pintype "passive"))
      (node (ref "U1") (pin "9") (pinfunction "OUT_9") (pintype "passive"))
    )
    (net (code "97") (name "Net-(U1-OVP)") (class "Default")
      (node (ref "R10") (pin "2") (pinfunction "2_2") (pintype "passive"))
      (node (ref "R13") (pin "1") (pinfunction "1_1") (pintype "passive"))
      (node (ref "U1") (pin "3") (pinfunction "OVP_3") (pintype "passive"))
    )
    (net (code "98") (name "Net-(U1-SENSE)") (class "Default")
      (node (ref "R7") (pin "2") (pinfunction "2_2") (pintype "passive"))
      (node (ref "U1") (pin "1") (pinfunction "SENSE_1") (pintype "passive"))
    )
    (net (code "99") (name "Net-(U1-TIMER)") (class "Default")
      (node (ref "C21") (pin "2") (pinfunction "2_2") (pintype "passive"))
      (node (ref "U1") (pin "7") (pinfunction "TIMER_7") (pintype "passive"))
    )
    (net (code "100") (name "Net-(U1-UVLO)") (class "Default")
      (node (ref "R10") (pin "1") (pinfunction "1_1") (pintype "passive"))
      (node (ref "R6") (pin "2") (pinfunction "2_2") (pintype "passive"))
      (node (ref "U1") (pin "4") (pinfunction "UVLO_4") (pintype "passive"))
    )
    (net (code "101") (name "Net-(U2-IN+)") (class "Default")
      (node (ref "C26") (pin "2") (pinfunction "2_2") (pintype "passive"))
      (node (ref "R19") (pin "1") (pinfunction "1_1") (pintype "passive"))
      (node (ref "U2") (pin "2") (pinfunction "IN+_2") (pintype "passive"))
    )
    (net (code "102") (name "Net-(U2-IN-)") (class "Default")
      (node (ref "C26") (pin "1") (pinfunction "1_1") (pintype "passive"))
      (node (ref "R25") (pin "1") (pinfunction "1_1") (pintype "passive"))
      (node (ref "U2") (pin "3") (pinfunction "IN-_3") (pintype "passive"))
    )
    (net (code "103") (name "Net-(U2-OUT)") (class "Default")
      (node (ref "R21") (pin "2") (pinfunction "2_2") (pintype "passive"))
      (node (ref "U2") (pin "8") (pinfunction "OUT_8") (pintype "passive"))
    )
    (net (code "104") (name "Net-(U3-IN+)") (class "Default")
      (node (ref "C27") (pin "2") (pinfunction "2_2") (pintype "passive"))
      (node (ref "R20") (pin "1") (pinfunction "1_1") (pintype "passive"))
      (node (ref "U3") (pin "2") (pinfunction "IN+_2") (pintype "passive"))
    )
    (net (code "105") (name "Net-(U3-IN-)") (class "Default")
      (node (ref "C27") (pin "1") (pinfunction "1_1") (pintype "passive"))
      (node (ref "R26") (pin "1") (pinfunction "1_1") (pintype "passive"))
      (node (ref "U3") (pin "3") (pinfunction "IN-_3") (pintype "passive"))
    )
    (net (code "106") (name "Net-(U3-OUT)") (class "Default")
      (node (ref "R22") (pin "2") (pinfunction "2_2") (pintype "passive"))
      (node (ref "U3") (pin "8") (pinfunction "OUT_8") (pintype "passive"))
    )
    (net (code "107") (name "Net-(U4-IN_A+)") (class "Default")
      (node (ref "R17") (pin "2") (pinfunction "2_2") (pintype "passive"))
      (node (ref "R23") (pin "1") (pinfunction "1_1") (pintype "passive"))
      (node (ref "U4") (pin "3") (pinfunction "IN_A+_3") (pintype "passive"))
    )
    (net (code "108") (name "Net-(U4-IN_A-)") (class "Default")
      (node (ref "R29") (pin "1") (pinfunction "1_1") (pintype "passive"))
      (node (ref "R31") (pin "2") (pinfunction "2_2") (pintype "passive"))
      (node (ref "U4") (pin "4") (pinfunction "IN_A-_4") (pintype "passive"))
    )
    (net (code "109") (name "Net-(U4-OUT_A)") (class "Default")
      (node (ref "R27") (pin "2") (pinfunction "2_2") (pintype "passive"))
      (node (ref "R31") (pin "1") (pinfunction "1_1") (pintype "passive"))
      (node (ref "U4") (pin "1") (pinfunction "OUT_A_1") (pintype "passive"))
    )
    (net (code "110") (name "Net-(U5-IN_A+)") (class "Default")
      (node (ref "R18") (pin "2") (pinfunction "2_2") (pintype "passive"))
      (node (ref "R24") (pin "1") (pinfunction "1_1") (pintype "passive"))
      (node (ref "U5") (pin "3") (pinfunction "IN_A+_3") (pintype "passive"))
    )
    (net (code "111") (name "Net-(U5-IN_A-)") (class "Default")
      (node (ref "R30") (pin "1") (pinfunction "1_1") (pintype "passive"))
      (node (ref "R32") (pin "2") (pinfunction "2_2") (pintype "passive"))
      (node (ref "U5") (pin "4") (pinfunction "IN_A-_4") (pintype "passive"))
    )
    (net (code "112") (name "Net-(U5-OUT_A)") (class "Default")
      (node (ref "R28") (pin "2") (pinfunction "2_2") (pintype "passive"))
      (node (ref "R32") (pin "1") (pinfunction "1_1") (pintype "passive"))
      (node (ref "U5") (pin "1") (pinfunction "OUT_A_1") (pintype "passive"))
    )
    (net (code "113") (name "Net-(U6-HB)") (class "Default")
      (node (ref "C32") (pin "2") (pinfunction "2_2") (pintype "passive"))
      (node (ref "U6") (pin "2") (pinfunction "HB_2") (pintype "passive"))
    )
    (net (code "114") (name "Net-(U6-HI)") (class "Default")
      (node (ref "R34") (pin "2") (pinfunction "2_2") (pintype "passive"))
      (node (ref "R37") (pin "1") (pinfunction "1_1") (pintype "passive"))
      (node (ref "U6") (pin "5") (pinfunction "HI_5") (pintype "passive"))
    )
    (net (code "115") (name "Net-(U6-HO)") (class "Default")
      (node (ref "R38") (pin "2") (pinfunction "2_2") (pintype "passive"))
      (node (ref "U6") (pin "3") (pinfunction "HO_3") (pintype "passive"))
    )
    (net (code "116") (name "Net-(U6-LI)") (class "Default")
      (node (ref "R41") (pin "1") (pinfunction "1_1") (pintype "passive"))
      (node (ref "R44") (pin "1") (pinfunction "1_1") (pintype "passive"))
      (node (ref "U6") (pin "6") (pinfunction "LI_6") (pintype "passive"))
    )
    (net (code "117") (name "Net-(U6-LO)") (class "Default")
      (node (ref "R45") (pin "2") (pinfunction "2_2") (pintype "passive"))
      (node (ref "U6") (pin "8") (pinfunction "LO_8") (pintype "passive"))
    )
    (net (code "118") (name "Net-(U7-HB)") (class "Default")
      (node (ref "C33") (pin "2") (pinfunction "2_2") (pintype "passive"))
      (node (ref "U7") (pin "2") (pinfunction "HB_2") (pintype "passive"))
    )
    (net (code "119") (name "Net-(U7-HI)") (class "Default")
      (node (ref "R35") (pin "2") (pinfunction "2_2") (pintype "passive"))
      (node (ref "R39") (pin "1") (pinfunction "1_1") (pintype "passive"))
      (node (ref "U7") (pin "5") (pinfunction "HI_5") (pintype "passive"))
    )
    (net (code "120") (name "Net-(U7-HO)") (class "Default")
      (node (ref "R40") (pin "2") (pinfunction "2_2") (pintype "passive"))
      (node (ref "U7") (pin "3") (pinfunction "HO_3") (pintype "passive"))
    )
    (net (code "121") (name "Net-(U7-LI)") (class "Default")
      (node (ref "R42") (pin "1") (pinfunction "1_1") (pintype "passive"))
      (node (ref "R46") (pin "1") (pinfunction "1_1") (pintype "passive"))
      (node (ref "U7") (pin "6") (pinfunction "LI_6") (pintype "passive"))
    )
    (net (code "122") (name "Net-(U7-LO)") (class "Default")
      (node (ref "R47") (pin "2") (pinfunction "2_2") (pintype "passive"))
      (node (ref "U7") (pin "8") (pinfunction "LO_8") (pintype "passive"))
    )
    (net (code "123") (name "Net-(U9-PB8-BOOT0)") (class "Default")
      (node (ref "R50") (pin "2") (pinfunction "2_2") (pintype "passive"))
      (node (ref "U9") (pin "45") (pinfunction "PB8-BOOT0_45") (pintype "passive"))
    )
    (net (code "124") (name "Net-(U9-PF0-OSC_IN)") (class "Default")
      (node (ref "U9") (pin "5") (pinfunction "PF0-OSC_IN_5") (pintype "passive"))
      (node (ref "X1") (pin "3") (pinfunction "OUT_3") (pintype "passive"))
    )
    (net (code "125") (name "Net-(U10-BOOT)") (class "Default")
      (node (ref "C53") (pin "1") (pinfunction "1_1") (pintype "passive"))
      (node (ref "U10") (pin "6") (pinfunction "BOOT_6") (pintype "passive"))
    )
    (net (code "126") (name "Net-(U10-EN)") (class "Default")
      (node (ref "R64") (pin "1") (pinfunction "1_1") (pintype "passive"))
      (node (ref "R67") (pin "2") (pinfunction "2_2") (pintype "passive"))
      (node (ref "U10") (pin "5") (pinfunction "EN_5") (pintype "passive"))
    )
    (net (code "127") (name "Net-(U10-FB)") (class "Default")
      (node (ref "R65") (pin "1") (pinfunction "1_1") (pintype "passive"))
      (node (ref "R68") (pin "2") (pinfunction "2_2") (pintype "passive"))
      (node (ref "U10") (pin "4") (pinfunction "FB_4") (pintype "passive"))
    )
    (net (code "128") (name "Net-(U10-SW)") (class "Default")
      (node (ref "C53") (pin "2") (pinfunction "2_2") (pintype "passive"))
      (node (ref "L3") (pin "1") (pinfunction "1_1") (pintype "passive"))
      (node (ref "U10") (pin "2") (pinfunction "SW_2") (pintype "passive"))
    )
    (net (code "129") (name "PGND") (class "Default")
      (node (ref "C10") (pin "1") (pinfunction "1_1") (pintype "passive"))
      (node (ref "C11") (pin "1") (pinfunction "1_1") (pintype "passive"))
      (node (ref "C12") (pin "1") (pinfunction "1_1") (pintype "passive"))
      (node (ref "C13") (pin "1") (pinfunction "1_1") (pintype "passive"))
      (node (ref "C14") (pin "1") (pinfunction "1_1") (pintype "passive"))
      (node (ref "C15") (pin "1") (pinfunction "1_1") (pintype "passive"))
      (node (ref "C16") (pin "1") (pinfunction "1_1") (pintype "passive"))
      (node (ref "C17") (pin "1") (pinfunction "1_1") (pintype "passive"))
      (node (ref "C18") (pin "1") (pinfunction "1_1") (pintype "passive"))
      (node (ref "C19") (pin "1") (pinfunction "1_1") (pintype "passive"))
      (node (ref "C2") (pin "1") (pinfunction "1_1") (pintype "passive"))
      (node (ref "C20") (pin "1") (pinfunction "1_1") (pintype "passive"))
      (node (ref "C21") (pin "1") (pinfunction "1_1") (pintype "passive"))
      (node (ref "C3") (pin "1") (pinfunction "1_1") (pintype "passive"))
      (node (ref "C4") (pin "1") (pinfunction "1_1") (pintype "passive"))
      (node (ref "C5") (pin "1") (pinfunction "1_1") (pintype "passive"))
      (node (ref "C6") (pin "1") (pinfunction "1_1") (pintype "passive"))
      (node (ref "C7") (pin "1") (pinfunction "1_1") (pintype "passive"))
      (node (ref "C8") (pin "1") (pinfunction "1_1") (pintype "passive"))
      (node (ref "C9") (pin "1") (pinfunction "1_1") (pintype "passive"))
      (node (ref "D6") (pin "1") (pinfunction "A_1") (pintype "passive"))
      (node (ref "D7") (pin "1") (pinfunction "A_1") (pintype "passive"))
      (node (ref "D8") (pin "1") (pinfunction "A_1") (pintype "passive"))
      (node (ref "FB3") (pin "2") (pinfunction "2_2") (pintype "passive"))
      (node (ref "P1") (pin "2") (pinfunction "2_2") (pintype "passive"))
      (node (ref "P2") (pin "2") (pinfunction "2_2") (pintype "passive"))
      (node (ref "P3") (pin "2") (pinfunction "2_2") (pintype "passive"))
      (node (ref "Q1") (pin "2") (pinfunction "E_2") (pintype "passive"))
      (node (ref "Q10") (pin "1") (pinfunction "S_1") (pintype "passive"))
      (node (ref "Q8") (pin "2") (pinfunction "E_2") (pintype "passive"))
      (node (ref "Q9") (pin "1") (pinfunction "S_1") (pintype "passive"))
      (node (ref "R13") (pin "2") (pinfunction "2_2") (pintype "passive"))
      (node (ref "R14") (pin "1") (pinfunction "1_1") (pintype "passive"))
      (node (ref "R15") (pin "1") (pinfunction "1_1") (pintype "passive"))
      (node (ref "R3") (pin "1") (pinfunction "1_1") (pintype "passive"))
      (node (ref "U1") (pin "6") (pinfunction "GND_6") (pintype "passive"))
    )
    (net (code "130") (name "VBAT_N") (class "Default")
      (node (ref "C40") (pin "2") (pinfunction "2_2") (pintype "passive"))
      (node (ref "C41") (pin "2") (pinfunction "2_2") (pintype "passive"))
      (node (ref "C42") (pin "2") (pinfunction "2_2") (pintype "passive"))
      (node (ref "D1") (pin "1") (pinfunction "C_1") (pintype "passive"))
      (node (ref "D4") (pin "2") (pinfunction "A_2") (pintype "passive"))
      (node (ref "Q2") (pin "3") (pinfunction "D_3") (pintype "passive"))
      (node (ref "R1") (pin "2") (pinfunction "2_2") (pintype "passive"))
      (node (ref "R23") (pin "2") (pinfunction "2_2") (pintype "passive"))
      (node (ref "R25") (pin "2") (pinfunction "2_2") (pintype "passive"))
      (node (ref "R6") (pin "1") (pinfunction "1_1") (pintype "passive"))
      (node (ref "R7") (pin "1") (pinfunction "1_1") (pintype "passive"))
      (node (ref "T1") (pin "2") (pinfunction "2_2") (pintype "passive"))
      (node (ref "T1") (pin "5") (pinfunction "5_5") (pintype "passive"))
      (node (ref "T16") (pin "7") (pinfunction "VIN_7") (pintype "passive"))
    )
    (net (code "131") (name "VBAT_P") (class "Default")
      (node (ref "C20") (pin "2") (pinfunction "2_2") (pintype "passive"))
      (node (ref "D6") (pin "2") (pinfunction "K_2") (pintype "passive"))
      (node (ref "P1") (pin "1") (pinfunction "1_1") (pintype "passive"))
      (node (ref "R1") (pin "1") (pinfunction "1_1") (pintype "passive"))
      (node (ref "R19") (pin "2") (pinfunction "2_2") (pintype "passive"))
    )
    (net (code "132") (name "VCAP_N") (class "Default")
      (node (ref "C14") (pin "2") (pinfunction "2_2") (pintype "passive"))
      (node (ref "C15") (pin "2") (pinfunction "2_2") (pintype "passive"))
      (node (ref "C16") (pin "2") (pinfunction "2_2") (pintype "passive"))
      (node (ref "C17") (pin "2") (pinfunction "2_2") (pintype "passive"))
      (node (ref "D7") (pin "2") (pinfunction "K_2") (pintype "passive"))
      (node (ref "P2") (pin "1") (pinfunction "1_1") (pintype "passive"))
      (node (ref "R24") (pin "2") (pinfunction "2_2") (pintype "passive"))
      (node (ref "R26") (pin "2") (pinfunction "2_2") (pintype "passive"))
      (node (ref "R4") (pin "2") (pinfunction "2_2") (pintype "passive"))
    )
    (net (code "133") (name "VCAP_P") (class "Default")
      (node (ref "C10") (pin "2") (pinfunction "2_2") (pintype "passive"))
      (node (ref "C11") (pin "2") (pinfunction "2_2") (pintype "passive"))
      (node (ref "C12") (pin "2") (pinfunction "2_2") (pintype "passive"))
      (node (ref "C13") (pin "2") (pinfunction "2_2") (pintype "passive"))
      (node (ref "Q5") (pin "3") (pinfunction "3_3") (pintype "passive"))
      (node (ref "R20") (pin "2") (pinfunction "2_2") (pintype "passive"))
      (node (ref "R4") (pin "1") (pinfunction "1_1") (pintype "passive"))
    )
    (net (code "134") (name "unconnected-(H6-Pad3)") (class "Default")
      (node (ref "H6") (pin "3") (pinfunction "3_3") (pintype "passive+no_connect"))
    )
    (net (code "135") (name "unconnected-(T16-ENA-Pad5)") (class "Default")
      (node (ref "T16") (pin "5") (pinfunction "ENA_5") (pintype "passive+no_connect"))
    )
    (net (code "136") (name "unconnected-(T16-NC-Pad2)") (class "Default")
      (node (ref "T16") (pin "2") (pinfunction "NC_2") (pintype "passive+no_connect"))
    )
    (net (code "137") (name "unconnected-(T16-NC-Pad3)") (class "Default")
      (node (ref "T16") (pin "3") (pinfunction "NC_3") (pintype "passive+no_connect"))
    )
    (net (code "138") (name "unconnected-(U1-nPGD-Pad8)") (class "Default")
      (node (ref "U1") (pin "8") (pinfunction "nPGD_8") (pintype "passive+no_connect"))
    )
    (net (code "139") (name "unconnected-(U2-NC-Pad1)") (class "Default")
      (node (ref "U2") (pin "1") (pinfunction "NC_1") (pintype "passive+no_connect"))
    )
    (net (code "140") (name "unconnected-(U3-NC-Pad1)") (class "Default")
      (node (ref "U3") (pin "1") (pinfunction "NC_1") (pintype "passive+no_connect"))
    )
    (net (code "141") (name "unconnected-(U8-RS-Pad8)") (class "Default")
      (node (ref "U8") (pin "8") (pinfunction "RS_8") (pintype "passive+no_connect"))
    )
    (net (code "142") (name "unconnected-(U8-SHDN-Pad5)") (class "Default")
      (node (ref "U8") (pin "5") (pinfunction "SHDN_5") (pintype "passive+no_connect"))
    )
    (net (code "143") (name "unconnected-(U9-PB1-Pad17)") (class "Default")
      (node (ref "U9") (pin "17") (pinfunction "PB1_17") (pintype "passive+no_connect"))
    )
    (net (code "144") (name "unconnected-(U9-PB2-Pad18)") (class "Default")
      (node (ref "U9") (pin "18") (pinfunction "PB2_18") (pintype "passive+no_connect"))
    )
    (net (code "145") (name "unconnected-(U9-PC13-Pad2)") (class "Default")
      (node (ref "U9") (pin "2") (pinfunction "PC13_2") (pintype "passive+no_connect"))
    )
    (net (code "146") (name "unconnected-(U9-PC14-OSC32_IN-Pad3)") (class "Default")
      (node (ref "U9") (pin "3") (pinfunction "PC14-OSC32_IN_3") (pintype "passive+no_connect"))
    )
    (net (code "147") (name "unconnected-(U9-PC15-OSC32_OUT-Pad4)") (class "Default")
      (node (ref "U9") (pin "4") (pinfunction "PC15-OSC32_OUT_4") (pintype "passive+no_connect"))
    )
    (net (code "148") (name "unconnected-(U9-PF1-OSC_OUT-Pad6)") (class "Default")
      (node (ref "U9") (pin "6") (pinfunction "PF1-OSC_OUT_6") (pintype "passive+no_connect"))
    )
    (net (code "149") (name "unconnected-(X1-OE-Pad1)") (class "Default")
      (node (ref "X1") (pin "1") (pinfunction "OE_1") (pintype "passive+no_connect"))
    )
  )
)
